# frontplatine_v0_2_140121.net
KiCad netlist of a schematic drawn in EAGLE
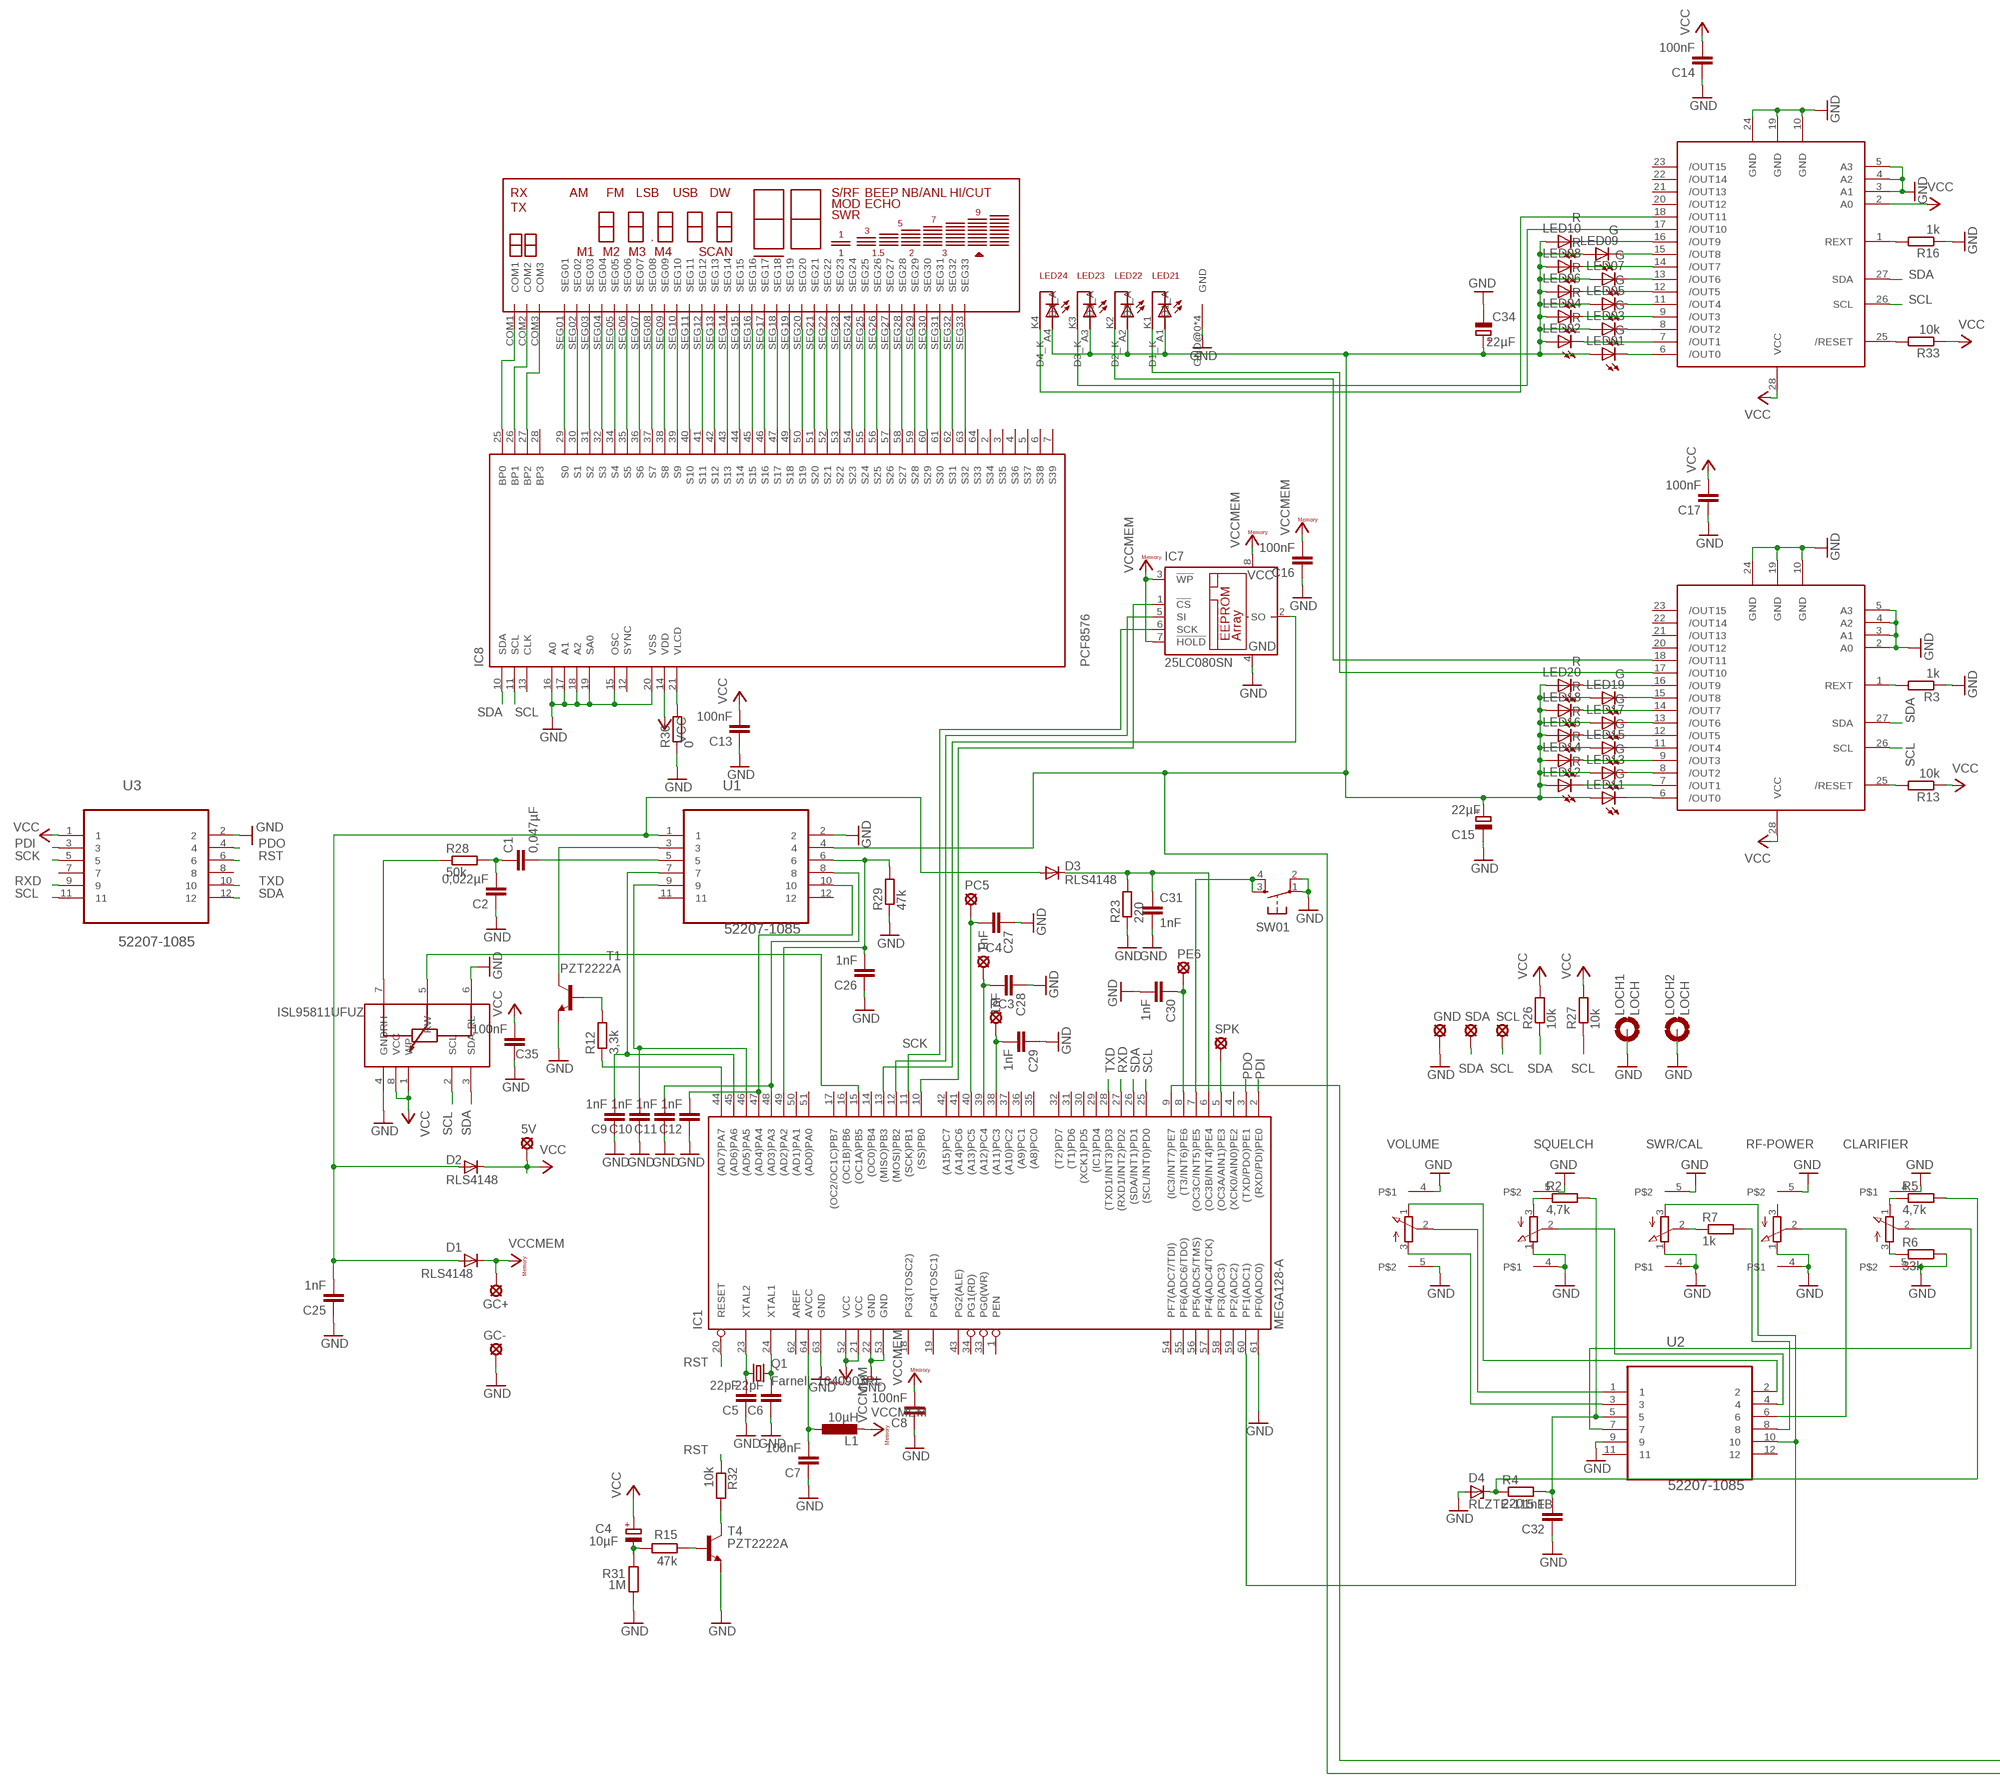
[diagram p0: schematic, sheet 1, part 1 of 2]
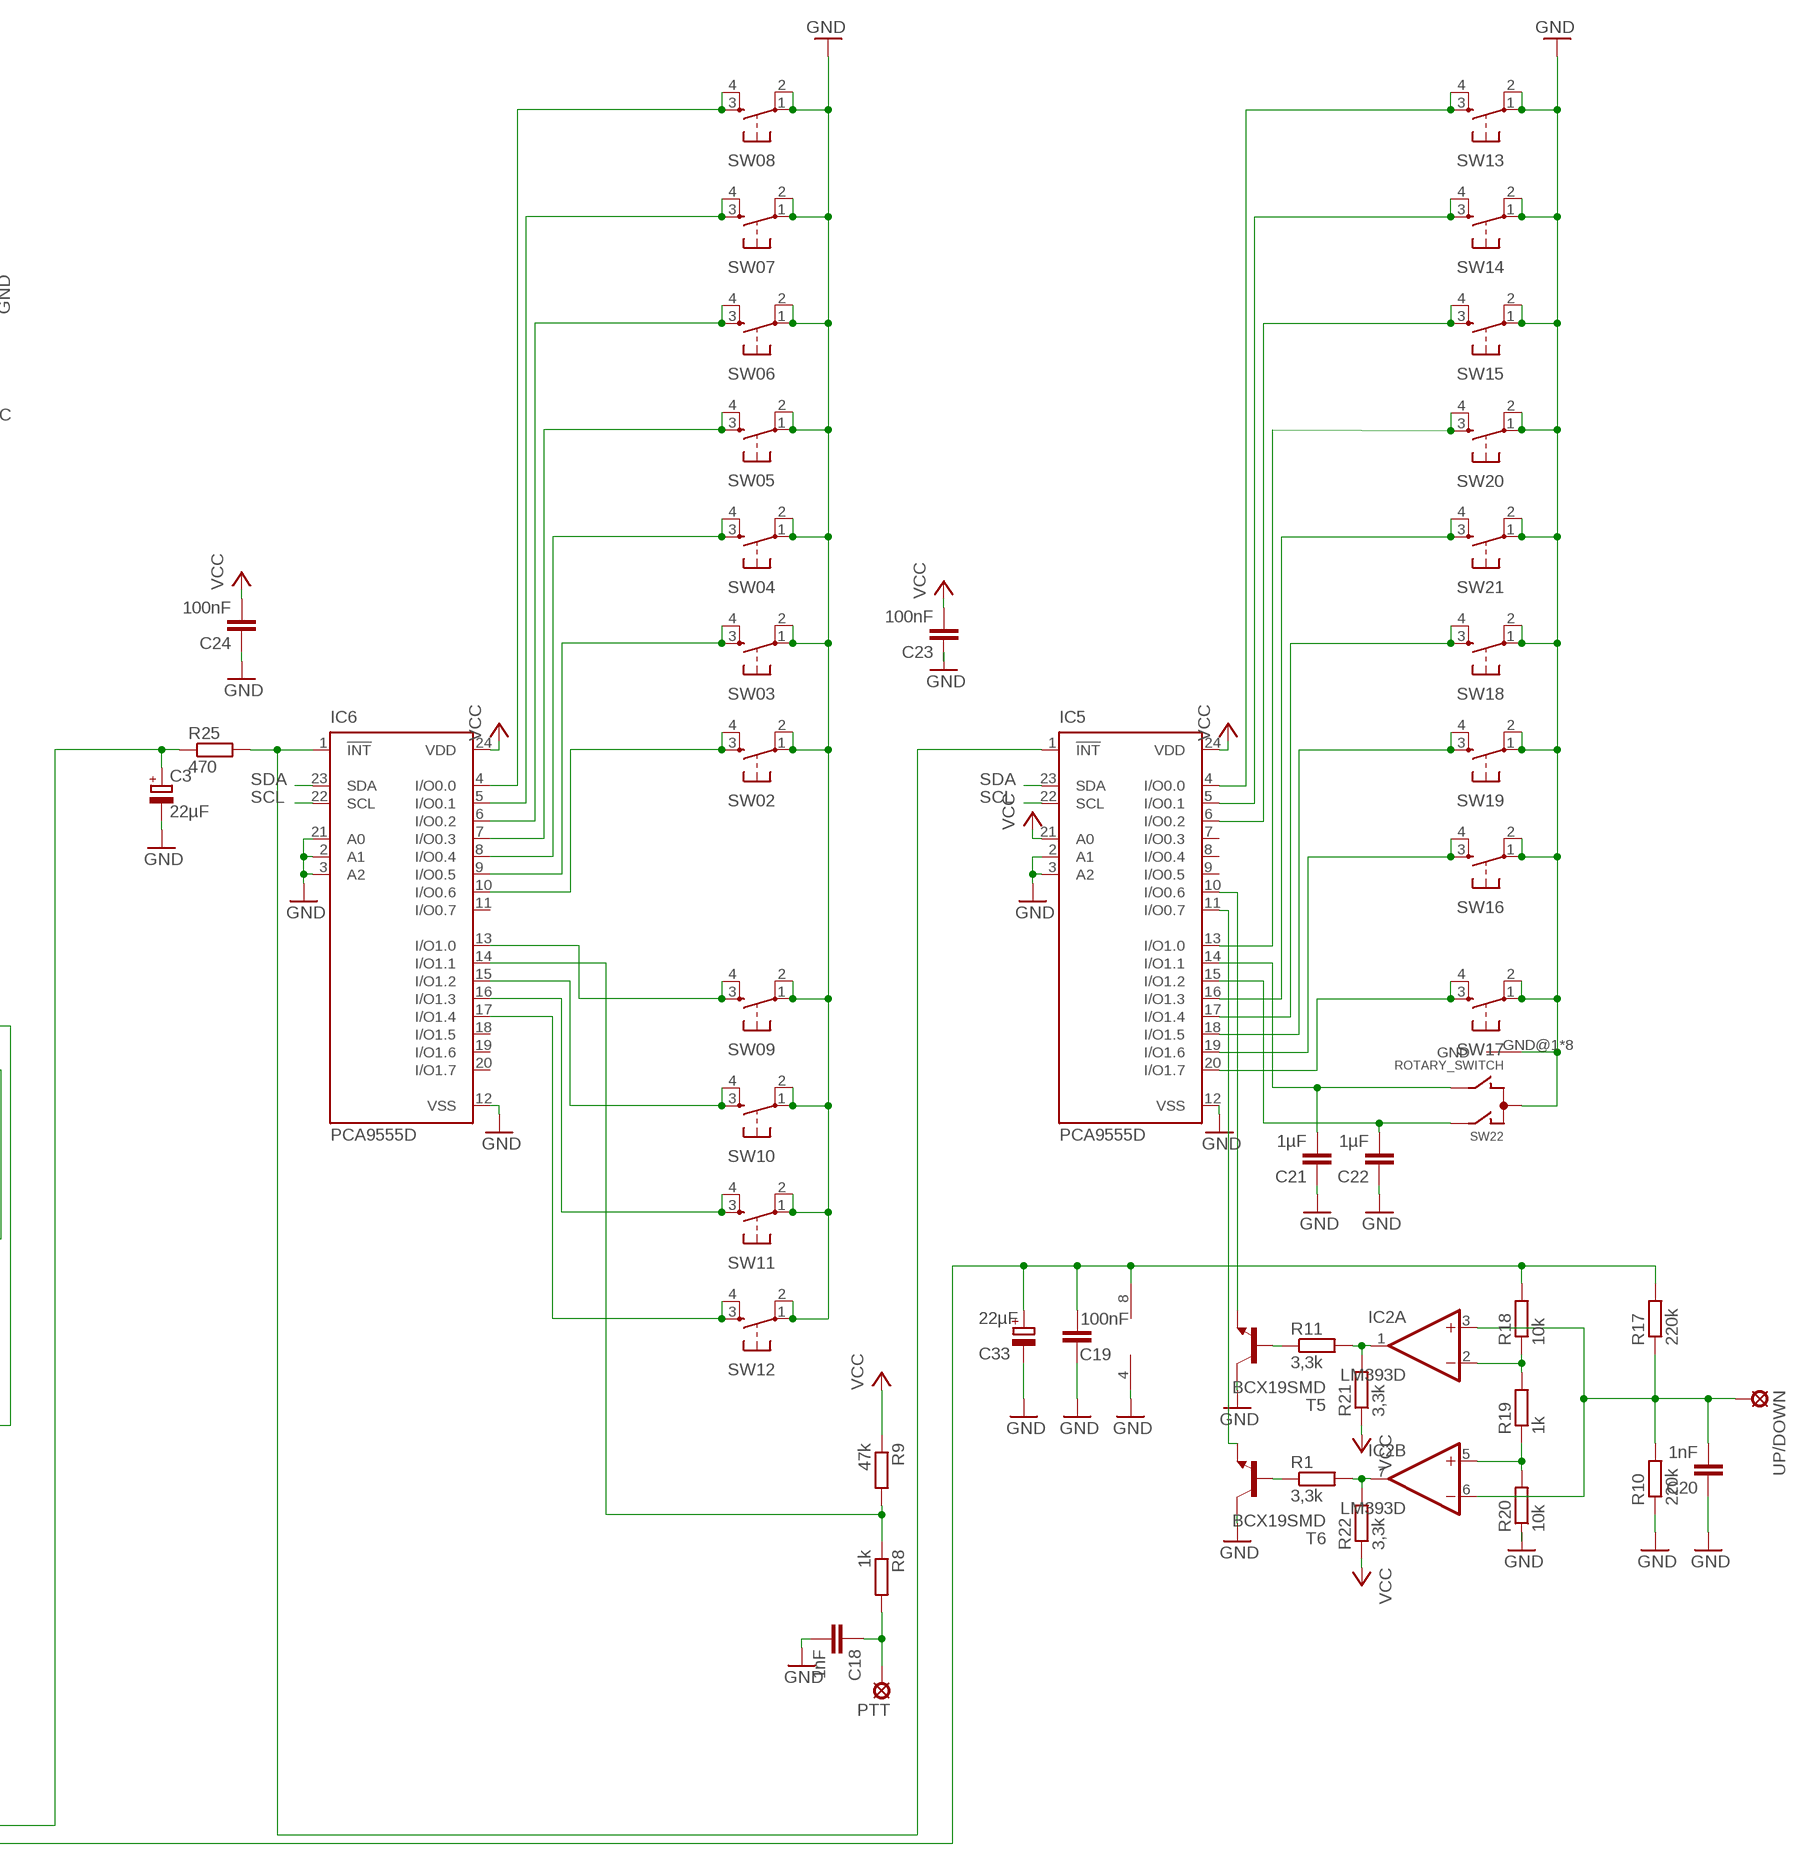
[diagram p1: schematic, sheet 1, part 2 of 2]

(export (version "E")
  (design (tool "Eeschema 10.0.6"))
  (components
    (comp (ref "5V")
      (value "SE11")
      (footprint "eagle-import:SE11")
      (libsource (lib "eagle-import") (part "SE11"))
    )
    (comp (ref "C1")
      (value "0,047µF")
      (footprint "eagle-import:C1206")
      (libsource (lib "eagle-import") (part "C-EUC1206"))
    )
    (comp (ref "C2")
      (value "0,022µF")
      (footprint "eagle-import:C1206")
      (libsource (lib "eagle-import") (part "resistor_C-EUC1206"))
    )
    (comp (ref "C3")
      (value "22µF")
      (footprint "eagle-import:CT3216")
      (libsource (lib "eagle-import") (part "CPOL-EUCT3216"))
    )
    (comp (ref "C4")
      (value "10µF")
      (footprint "eagle-import:CT3216")
      (libsource (lib "eagle-import") (part "CPOL-EUCT3216"))
    )
    (comp (ref "C5")
      (value "22pF")
      (footprint "eagle-import:C1206")
      (libsource (lib "eagle-import") (part "resistor_C-EUC1206"))
    )
    (comp (ref "C6")
      (value "22pF")
      (footprint "eagle-import:C1206")
      (libsource (lib "eagle-import") (part "resistor_C-EUC1206"))
    )
    (comp (ref "C7")
      (value "100nF")
      (footprint "eagle-import:C1206")
      (libsource (lib "eagle-import") (part "resistor_C-EUC1206"))
    )
    (comp (ref "C8")
      (value "100nF")
      (footprint "eagle-import:C1206")
      (libsource (lib "eagle-import") (part "resistor_C-EUC1206"))
    )
    (comp (ref "C9")
      (value "1nF")
      (footprint "eagle-import:C1206")
      (libsource (lib "eagle-import") (part "resistor_C-EUC1206"))
    )
    (comp (ref "C10")
      (value "1nF")
      (footprint "eagle-import:C1206")
      (libsource (lib "eagle-import") (part "resistor_C-EUC1206"))
    )
    (comp (ref "C11")
      (value "1nF")
      (footprint "eagle-import:C1206")
      (libsource (lib "eagle-import") (part "resistor_C-EUC1206"))
    )
    (comp (ref "C12")
      (value "1nF")
      (footprint "eagle-import:C1206")
      (libsource (lib "eagle-import") (part "resistor_C-EUC1206"))
    )
    (comp (ref "C13")
      (value "100nF")
      (footprint "eagle-import:C1206")
      (libsource (lib "eagle-import") (part "resistor_C-EUC1206"))
    )
    (comp (ref "C14")
      (value "100nF")
      (footprint "eagle-import:C1206")
      (libsource (lib "eagle-import") (part "resistor_C-EUC1206"))
    )
    (comp (ref "C15")
      (value "22µF")
      (footprint "eagle-import:CT3216")
      (libsource (lib "eagle-import") (part "CPOL-EUCT3216"))
    )
    (comp (ref "C16")
      (value "100nF")
      (footprint "eagle-import:C1206")
      (libsource (lib "eagle-import") (part "resistor_C-EUC1206"))
    )
    (comp (ref "C17")
      (value "100nF")
      (footprint "eagle-import:C1206")
      (libsource (lib "eagle-import") (part "resistor_C-EUC1206"))
    )
    (comp (ref "C18")
      (value "1nF")
      (footprint "eagle-import:C1206")
      (libsource (lib "eagle-import") (part "resistor_C-EUC1206"))
    )
    (comp (ref "C19")
      (value "100nF")
      (footprint "eagle-import:C1206")
      (libsource (lib "eagle-import") (part "resistor_C-EUC1206"))
    )
    (comp (ref "C20")
      (value "1nF")
      (footprint "eagle-import:C1206")
      (libsource (lib "eagle-import") (part "resistor_C-EUC1206"))
    )
    (comp (ref "C21")
      (value "1µF")
      (footprint "eagle-import:C1206")
      (libsource (lib "eagle-import") (part "resistor_C-EUC1206"))
    )
    (comp (ref "C22")
      (value "1µF")
      (footprint "eagle-import:C1206")
      (libsource (lib "eagle-import") (part "resistor_C-EUC1206"))
    )
    (comp (ref "C23")
      (value "100nF")
      (footprint "eagle-import:C1206")
      (libsource (lib "eagle-import") (part "resistor_C-EUC1206"))
    )
    (comp (ref "C24")
      (value "100nF")
      (footprint "eagle-import:C1206")
      (libsource (lib "eagle-import") (part "resistor_C-EUC1206"))
    )
    (comp (ref "C25")
      (value "1nF")
      (footprint "eagle-import:C1206")
      (libsource (lib "eagle-import") (part "resistor_C-EUC1206"))
    )
    (comp (ref "C26")
      (value "1nF")
      (footprint "eagle-import:C1206")
      (libsource (lib "eagle-import") (part "resistor_C-EUC1206"))
    )
    (comp (ref "C27")
      (value "1nF")
      (footprint "eagle-import:C1206")
      (libsource (lib "eagle-import") (part "resistor_C-EUC1206"))
    )
    (comp (ref "C28")
      (value "1nF")
      (footprint "eagle-import:C1206")
      (libsource (lib "eagle-import") (part "resistor_C-EUC1206"))
    )
    (comp (ref "C29")
      (value "1nF")
      (footprint "eagle-import:C1206")
      (libsource (lib "eagle-import") (part "resistor_C-EUC1206"))
    )
    (comp (ref "C30")
      (value "1nF")
      (footprint "eagle-import:C1206")
      (libsource (lib "eagle-import") (part "resistor_C-EUC1206"))
    )
    (comp (ref "C31")
      (value "1nF")
      (footprint "eagle-import:C1206")
      (libsource (lib "eagle-import") (part "resistor_C-EUC1206"))
    )
    (comp (ref "C32")
      (value "1nF")
      (footprint "eagle-import:C1206")
      (libsource (lib "eagle-import") (part "resistor_C-EUC1206"))
    )
    (comp (ref "C33")
      (value "22µF")
      (footprint "eagle-import:CT3216")
      (libsource (lib "eagle-import") (part "CPOL-EUCT3216"))
    )
    (comp (ref "C34")
      (value "22µF")
      (footprint "eagle-import:CT3216")
      (libsource (lib "eagle-import") (part "CPOL-EUCT3216"))
    )
    (comp (ref "C35")
      (value "100nF")
      (footprint "eagle-import:C1206")
      (libsource (lib "eagle-import") (part "resistor_C-EUC1206"))
    )
    (comp (ref "CLARIFIER")
      (value "POTI")
      (footprint "eagle-import:POTI")
      (libsource (lib "eagle-import") (part "POTI"))
    )
    (comp (ref "D1")
      (value "RLS4148")
      (footprint "eagle-import:SOD80C")
      (libsource (lib "eagle-import") (part "DIODE-SOD80C"))
    )
    (comp (ref "D2")
      (value "RLS4148")
      (footprint "eagle-import:SOD80C")
      (libsource (lib "eagle-import") (part "DIODE-SOD80C"))
    )
    (comp (ref "D3")
      (value "RLS4148")
      (footprint "eagle-import:SOD80C")
      (libsource (lib "eagle-import") (part "DIODE-SOD80C"))
    )
    (comp (ref "D4")
      (value "RLZTE-115.1B")
      (footprint "eagle-import:SOD80C")
      (libsource (lib "eagle-import") (part "ZENER-DIODESOD80C"))
    )
    (comp (ref "DISPLAY1")
      (value "DISPLAY")
      (footprint "eagle-import:DISPLAY")
      (libsource (lib "eagle-import") (part "DISPLAY"))
    )
    (comp (ref "GC+")
      (value "SE11")
      (footprint "eagle-import:SE11")
      (libsource (lib "eagle-import") (part "SE11"))
    )
    (comp (ref "GC-")
      (value "SE11")
      (footprint "eagle-import:SE11")
      (libsource (lib "eagle-import") (part "SE11"))
    )
    (comp (ref "GND")
      (value "SE11")
      (footprint "eagle-import:SE11")
      (libsource (lib "eagle-import") (part "SE11"))
    )
    (comp (ref "IC1")
      (value "MEGA128-A")
      (footprint "eagle-import:TQFP64")
      (fields (field (name "MPN") "ATMEGA128-16AU"))
      (libsource (lib "eagle-import") (part "MEGA128-A"))
    )
    (comp (ref "IC2")
      (value "LM393D")
      (footprint "eagle-import:SO08")
      (libsource (lib "eagle-import") (part "LM393D"))
    )
    (comp (ref "IC3")
      (value "TLC59116")
      (footprint "eagle-import:TSSOP28")
      (libsource (lib "eagle-import") (part "TLC59116"))
    )
    (comp (ref "IC4")
      (value "TLC59116")
      (footprint "eagle-import:TSSOP28")
      (libsource (lib "eagle-import") (part "TLC59116"))
    )
    (comp (ref "IC5")
      (value "PCA9555D")
      (footprint "eagle-import:SO24")
      (fields (field (name "MPN") "PCA9555DW"))
      (libsource (lib "eagle-import") (part "PCA9555D"))
    )
    (comp (ref "IC6")
      (value "PCA9555D")
      (footprint "eagle-import:SO24")
      (fields (field (name "MPN") "PCA9555DW"))
      (libsource (lib "eagle-import") (part "PCA9555D"))
    )
    (comp (ref "IC7")
      (value "25LC080SN")
      (footprint "eagle-import:SO-08")
      (fields
        (field (name "MF") "MICROCHIP")
        (field (name "MPN") "25LC080/SN")
        (field (name "MPN_1") "25LC080/SN")
        (field (name "OC_FARNELL") "1137302")
        (field (name "OC_NEWARK") "96K4092")
      )
      (libsource (lib "eagle-import") (part "25SNLC080"))
    )
    (comp (ref "IC8")
      (value "PCF8576")
      (footprint "eagle-import:LQFP-ST-64-2")
      (libsource (lib "eagle-import") (part "PCF8576"))
    )
    (comp (ref "L1")
      (value "10µH")
      (footprint "eagle-import:L1812")
      (libsource (lib "eagle-import") (part "L-EUL1812"))
    )
    (comp (ref "LED01")
      (value "G")
      (footprint "eagle-import:CHIPLED_1206")
      (libsource (lib "eagle-import") (part "LEDCHIPLED_1206"))
    )
    (comp (ref "LED02")
      (value "R")
      (footprint "eagle-import:CHIPLED_1206")
      (libsource (lib "eagle-import") (part "LEDCHIPLED_1206"))
    )
    (comp (ref "LED03")
      (value "G")
      (footprint "eagle-import:CHIPLED_1206")
      (libsource (lib "eagle-import") (part "LEDCHIPLED_1206"))
    )
    (comp (ref "LED04")
      (value "R")
      (footprint "eagle-import:CHIPLED_1206")
      (libsource (lib "eagle-import") (part "LEDCHIPLED_1206"))
    )
    (comp (ref "LED05")
      (value "G")
      (footprint "eagle-import:CHIPLED_1206")
      (libsource (lib "eagle-import") (part "LEDCHIPLED_1206"))
    )
    (comp (ref "LED06")
      (value "R")
      (footprint "eagle-import:CHIPLED_1206")
      (libsource (lib "eagle-import") (part "LEDCHIPLED_1206"))
    )
    (comp (ref "LED07")
      (value "G")
      (footprint "eagle-import:CHIPLED_1206")
      (libsource (lib "eagle-import") (part "LEDCHIPLED_1206"))
    )
    (comp (ref "LED08")
      (value "R")
      (footprint "eagle-import:CHIPLED_1206")
      (libsource (lib "eagle-import") (part "LEDCHIPLED_1206"))
    )
    (comp (ref "LED09")
      (value "G")
      (footprint "eagle-import:CHIPLED_1206")
      (libsource (lib "eagle-import") (part "LEDCHIPLED_1206"))
    )
    (comp (ref "LED10")
      (value "R")
      (footprint "eagle-import:CHIPLED_1206")
      (libsource (lib "eagle-import") (part "LEDCHIPLED_1206"))
    )
    (comp (ref "LED11")
      (value "G")
      (footprint "eagle-import:CHIPLED_1206")
      (libsource (lib "eagle-import") (part "LEDCHIPLED_1206"))
    )
    (comp (ref "LED12")
      (value "R")
      (footprint "eagle-import:CHIPLED_1206")
      (libsource (lib "eagle-import") (part "LEDCHIPLED_1206"))
    )
    (comp (ref "LED13")
      (value "G")
      (footprint "eagle-import:CHIPLED_1206")
      (libsource (lib "eagle-import") (part "LEDCHIPLED_1206"))
    )
    (comp (ref "LED14")
      (value "R")
      (footprint "eagle-import:CHIPLED_1206")
      (libsource (lib "eagle-import") (part "LEDCHIPLED_1206"))
    )
    (comp (ref "LED15")
      (value "G")
      (footprint "eagle-import:CHIPLED_1206")
      (libsource (lib "eagle-import") (part "LEDCHIPLED_1206"))
    )
    (comp (ref "LED16")
      (value "R")
      (footprint "eagle-import:CHIPLED_1206")
      (libsource (lib "eagle-import") (part "LEDCHIPLED_1206"))
    )
    (comp (ref "LED17")
      (value "G")
      (footprint "eagle-import:CHIPLED_1206")
      (libsource (lib "eagle-import") (part "LEDCHIPLED_1206"))
    )
    (comp (ref "LED18")
      (value "R")
      (footprint "eagle-import:CHIPLED_1206")
      (libsource (lib "eagle-import") (part "LEDCHIPLED_1206"))
    )
    (comp (ref "LED19")
      (value "G")
      (footprint "eagle-import:CHIPLED_1206")
      (libsource (lib "eagle-import") (part "LEDCHIPLED_1206"))
    )
    (comp (ref "LED20")
      (value "R")
      (footprint "eagle-import:CHIPLED_1206")
      (libsource (lib "eagle-import") (part "LEDCHIPLED_1206"))
    )
    (comp (ref "LOCH1")
      (value "LOCH")
      (footprint "eagle-import:LOCH")
      (libsource (lib "eagle-import") (part "LOCH"))
    )
    (comp (ref "LOCH2")
      (value "LOCH")
      (footprint "eagle-import:LOCH")
      (libsource (lib "eagle-import") (part "LOCH"))
    )
    (comp (ref "PC3")
      (value "SE11")
      (footprint "eagle-import:SE11")
      (libsource (lib "eagle-import") (part "SE11"))
    )
    (comp (ref "PC4")
      (value "SE11")
      (footprint "eagle-import:SE11")
      (libsource (lib "eagle-import") (part "SE11"))
    )
    (comp (ref "PC5")
      (value "SE11")
      (footprint "eagle-import:SE11")
      (libsource (lib "eagle-import") (part "SE11"))
    )
    (comp (ref "PE6")
      (value "SE11")
      (footprint "eagle-import:SE11")
      (libsource (lib "eagle-import") (part "SE11"))
    )
    (comp (ref "PTT")
      (value "SE11")
      (footprint "eagle-import:SE11")
      (libsource (lib "eagle-import") (part "SE11"))
    )
    (comp (ref "Q1")
      (value "Farnell: 1640903RL")
      (footprint "eagle-import:HC49UP")
      (libsource (lib "eagle-import") (part "CRYSTALHC49UP"))
    )
    (comp (ref "R1")
      (value "3,3k")
      (footprint "eagle-import:R1206")
      (libsource (lib "eagle-import") (part "resistor_R-EU_R1206"))
    )
    (comp (ref "R2")
      (value "4,7k")
      (footprint "eagle-import:R1206")
      (libsource (lib "eagle-import") (part "resistor_R-EU_R1206"))
    )
    (comp (ref "R3")
      (value "1k")
      (footprint "eagle-import:R1206")
      (libsource (lib "eagle-import") (part "R-EU_R1206"))
    )
    (comp (ref "R4")
      (value "220")
      (footprint "eagle-import:R1206")
      (libsource (lib "eagle-import") (part "resistor_R-EU_R1206"))
    )
    (comp (ref "R5")
      (value "4,7k")
      (footprint "eagle-import:R1206")
      (libsource (lib "eagle-import") (part "resistor_R-EU_R1206"))
    )
    (comp (ref "R6")
      (value "33k")
      (footprint "eagle-import:R1206")
      (libsource (lib "eagle-import") (part "resistor_R-EU_R1206"))
    )
    (comp (ref "R7")
      (value "1k")
      (footprint "eagle-import:R1206")
      (libsource (lib "eagle-import") (part "resistor_R-EU_R1206"))
    )
    (comp (ref "R8")
      (value "1k")
      (footprint "eagle-import:R1206")
      (libsource (lib "eagle-import") (part "resistor_R-EU_R1206"))
    )
    (comp (ref "R9")
      (value "47k")
      (footprint "eagle-import:R1206")
      (libsource (lib "eagle-import") (part "resistor_R-EU_R1206"))
    )
    (comp (ref "R10")
      (value "220k")
      (footprint "eagle-import:R1206")
      (libsource (lib "eagle-import") (part "resistor_R-EU_R1206"))
    )
    (comp (ref "R11")
      (value "3,3k")
      (footprint "eagle-import:R1206")
      (libsource (lib "eagle-import") (part "resistor_R-EU_R1206"))
    )
    (comp (ref "R12")
      (value "3,3k")
      (footprint "eagle-import:R1206")
      (libsource (lib "eagle-import") (part "resistor_R-EU_R1206"))
    )
    (comp (ref "R13")
      (value "10k")
      (footprint "eagle-import:R1206")
      (libsource (lib "eagle-import") (part "resistor_R-EU_R1206"))
    )
    (comp (ref "R15")
      (value "47k")
      (footprint "eagle-import:R1206")
      (libsource (lib "eagle-import") (part "resistor_R-EU_R1206"))
    )
    (comp (ref "R16")
      (value "1k")
      (footprint "eagle-import:R1206")
      (libsource (lib "eagle-import") (part "R-EU_R1206"))
    )
    (comp (ref "R17")
      (value "220k")
      (footprint "eagle-import:R1206")
      (libsource (lib "eagle-import") (part "resistor_R-EU_R1206"))
    )
    (comp (ref "R18")
      (value "10k")
      (footprint "eagle-import:R1206")
      (libsource (lib "eagle-import") (part "resistor_R-EU_R1206"))
    )
    (comp (ref "R19")
      (value "1k")
      (footprint "eagle-import:R1206")
      (libsource (lib "eagle-import") (part "resistor_R-EU_R1206"))
    )
    (comp (ref "R20")
      (value "10k")
      (footprint "eagle-import:R1206")
      (libsource (lib "eagle-import") (part "resistor_R-EU_R1206"))
    )
    (comp (ref "R21")
      (value "3,3k")
      (footprint "eagle-import:R1206")
      (libsource (lib "eagle-import") (part "resistor_R-EU_R1206"))
    )
    (comp (ref "R22")
      (value "3,3k")
      (footprint "eagle-import:R1206")
      (libsource (lib "eagle-import") (part "resistor_R-EU_R1206"))
    )
    (comp (ref "R23")
      (value "220")
      (footprint "eagle-import:R1206")
      (libsource (lib "eagle-import") (part "resistor_R-EU_R1206"))
    )
    (comp (ref "R25")
      (value "470")
      (footprint "eagle-import:R1206")
      (libsource (lib "eagle-import") (part "resistor_R-EU_R1206"))
    )
    (comp (ref "R26")
      (value "10k")
      (footprint "eagle-import:R1206")
      (libsource (lib "eagle-import") (part "resistor_R-EU_R1206"))
    )
    (comp (ref "R27")
      (value "10k")
      (footprint "eagle-import:R1206")
      (libsource (lib "eagle-import") (part "resistor_R-EU_R1206"))
    )
    (comp (ref "R28")
      (value "50k")
      (footprint "eagle-import:R1206")
      (libsource (lib "eagle-import") (part "resistor_R-EU_R1206"))
    )
    (comp (ref "R29")
      (value "47k")
      (footprint "eagle-import:R1206")
      (libsource (lib "eagle-import") (part "resistor_R-EU_R1206"))
    )
    (comp (ref "R30")
      (value "0")
      (footprint "eagle-import:R1206")
      (libsource (lib "eagle-import") (part "resistor_R-EU_R1206"))
    )
    (comp (ref "R31")
      (value "1M")
      (footprint "eagle-import:R1206")
      (libsource (lib "eagle-import") (part "resistor_R-EU_R1206"))
    )
    (comp (ref "R32")
      (value "10k")
      (footprint "eagle-import:R1206")
      (libsource (lib "eagle-import") (part "resistor_R-EU_R1206"))
    )
    (comp (ref "R33")
      (value "10k")
      (footprint "eagle-import:R1206")
      (libsource (lib "eagle-import") (part "resistor_R-EU_R1206"))
    )
    (comp (ref "RF-POWER")
      (value "POTI")
      (footprint "eagle-import:POTI")
      (libsource (lib "eagle-import") (part "POTI"))
    )
    (comp (ref "SCL")
      (value "SE11")
      (footprint "eagle-import:SE11")
      (libsource (lib "eagle-import") (part "SE11"))
    )
    (comp (ref "SDA")
      (value "SE11")
      (footprint "eagle-import:SE11")
      (libsource (lib "eagle-import") (part "SE11"))
    )
    (comp (ref "SPK")
      (value "SE11")
      (footprint "eagle-import:SE11")
      (libsource (lib "eagle-import") (part "SE11"))
    )
    (comp (ref "SQUELCH")
      (value "POTI")
      (footprint "eagle-import:POTI")
      (libsource (lib "eagle-import") (part "POTI"))
    )
    (comp (ref "SW01")
      (value "TASTER")
      (footprint "eagle-import:TASTER")
      (libsource (lib "eagle-import") (part "TASTER"))
    )
    (comp (ref "SW02")
      (value "TASTER")
      (footprint "eagle-import:TASTER")
      (libsource (lib "eagle-import") (part "TASTER"))
    )
    (comp (ref "SW03")
      (value "TASTER")
      (footprint "eagle-import:TASTER")
      (libsource (lib "eagle-import") (part "TASTER"))
    )
    (comp (ref "SW04")
      (value "TASTER")
      (footprint "eagle-import:TASTER")
      (libsource (lib "eagle-import") (part "TASTER"))
    )
    (comp (ref "SW05")
      (value "TASTER")
      (footprint "eagle-import:TASTER")
      (libsource (lib "eagle-import") (part "TASTER"))
    )
    (comp (ref "SW06")
      (value "TASTER")
      (footprint "eagle-import:TASTER")
      (libsource (lib "eagle-import") (part "TASTER"))
    )
    (comp (ref "SW07")
      (value "TASTER")
      (footprint "eagle-import:TASTER")
      (libsource (lib "eagle-import") (part "TASTER"))
    )
    (comp (ref "SW08")
      (value "TASTER")
      (footprint "eagle-import:TASTER")
      (libsource (lib "eagle-import") (part "TASTER"))
    )
    (comp (ref "SW09")
      (value "TASTER")
      (footprint "eagle-import:TASTER")
      (libsource (lib "eagle-import") (part "TASTER"))
    )
    (comp (ref "SW10")
      (value "TASTER")
      (footprint "eagle-import:TASTER")
      (libsource (lib "eagle-import") (part "TASTER"))
    )
    (comp (ref "SW11")
      (value "TASTER")
      (footprint "eagle-import:TASTER")
      (libsource (lib "eagle-import") (part "TASTER"))
    )
    (comp (ref "SW12")
      (value "TASTER")
      (footprint "eagle-import:TASTER")
      (libsource (lib "eagle-import") (part "TASTER"))
    )
    (comp (ref "SW13")
      (value "TASTER")
      (footprint "eagle-import:TASTER")
      (libsource (lib "eagle-import") (part "TASTER"))
    )
    (comp (ref "SW14")
      (value "TASTER")
      (footprint "eagle-import:TASTER")
      (libsource (lib "eagle-import") (part "TASTER"))
    )
    (comp (ref "SW15")
      (value "TASTER")
      (footprint "eagle-import:TASTER")
      (libsource (lib "eagle-import") (part "TASTER"))
    )
    (comp (ref "SW16")
      (value "TASTER")
      (footprint "eagle-import:TASTER")
      (libsource (lib "eagle-import") (part "TASTER"))
    )
    (comp (ref "SW17")
      (value "TASTER")
      (footprint "eagle-import:TASTER")
      (libsource (lib "eagle-import") (part "TASTER"))
    )
    (comp (ref "SW18")
      (value "TASTER")
      (footprint "eagle-import:TASTER")
      (libsource (lib "eagle-import") (part "TASTER"))
    )
    (comp (ref "SW19")
      (value "TASTER")
      (footprint "eagle-import:TASTER")
      (libsource (lib "eagle-import") (part "TASTER"))
    )
    (comp (ref "SW20")
      (value "TASTER")
      (footprint "eagle-import:TASTER")
      (libsource (lib "eagle-import") (part "TASTER"))
    )
    (comp (ref "SW21")
      (value "TASTER")
      (footprint "eagle-import:TASTER")
      (libsource (lib "eagle-import") (part "TASTER"))
    )
    (comp (ref "SW22")
      (value "ROTARY_SWITCH")
      (footprint "eagle-import:ROTARY_SWITCH")
      (libsource (lib "eagle-import") (part "ROTARY_SWITCH"))
    )
    (comp (ref "SWR/CAL")
      (value "POTI")
      (footprint "eagle-import:POTI")
      (libsource (lib "eagle-import") (part "POTI"))
    )
    (comp (ref "T1")
      (value "PZT2222A")
      (footprint "eagle-import:SOT223")
      (libsource (lib "eagle-import") (part "-NPN-SOT223PZT2222A"))
    )
    (comp (ref "T4")
      (value "PZT2222A")
      (footprint "eagle-import:SOT223")
      (libsource (lib "eagle-import") (part "-NPN-SOT223PZT2222A"))
    )
    (comp (ref "T5")
      (value "BCX19SMD")
      (footprint "eagle-import:SOT23-BEC")
      (libsource (lib "eagle-import") (part "BCX19SMD"))
    )
    (comp (ref "T6")
      (value "BCX19SMD")
      (footprint "eagle-import:SOT23-BEC")
      (libsource (lib "eagle-import") (part "BCX19SMD"))
    )
    (comp (ref "U$1")
      (value "ISL95811UFUZ")
      (footprint "eagle-import:MSOP8")
      (libsource (lib "eagle-import") (part "ISL95811UFUZ"))
    )
    (comp (ref "U1")
      (value "52207-1085")
      (footprint "eagle-import:MOLEX_52207-1085")
      (fields
        (field (name "MPN") "52207-1085")
        (field (name "OC_FARNELL") "1079938")
        (field (name "OC_NEWARK") "58J9503")
        (field (name "PACKAGE") "SOCKET FPC, SMT, 1MM, 10 WAY")
      )
      (libsource (lib "eagle-import") (part "52207-1085"))
    )
    (comp (ref "U2")
      (value "52207-1085")
      (footprint "eagle-import:MOLEX_52207-1085")
      (fields
        (field (name "MPN") "52207-1085")
        (field (name "OC_FARNELL") "1079938")
        (field (name "OC_NEWARK") "58J9503")
        (field (name "PACKAGE") "SOCKET FPC, SMT, 1MM, 10 WAY")
      )
      (libsource (lib "eagle-import") (part "52207-1085"))
    )
    (comp (ref "U3")
      (value "52207-1085")
      (footprint "eagle-import:MOLEX_52207-1085")
      (libsource (lib "eagle-import") (part "52207-1085"))
    )
    (comp (ref "UP/DOWN")
      (value "SE11")
      (footprint "eagle-import:SE11")
      (libsource (lib "eagle-import") (part "SE11"))
    )
    (comp (ref "VOLUME")
      (value "POTI")
      (footprint "eagle-import:POTI")
      (libsource (lib "eagle-import") (part "POTI"))
    )
  )
  (nets
    (net (code "1") (name "/PDI") (class "Default")
      (node (ref "IC1") (pin "2") (pinfunction "(RXD/PDI)PE0_2") (pintype "bidirectional"))
      (node (ref "U3") (pin "3") (pinfunction "3_3") (pintype "passive"))
    )
    (net (code "2") (name "/PDO") (class "Default")
      (node (ref "IC1") (pin "3") (pinfunction "(TXD/PDO)PE1_3") (pintype "bidirectional"))
      (node (ref "U3") (pin "4") (pinfunction "4_4") (pintype "passive"))
    )
    (net (code "3") (name "/RST") (class "Default")
      (node (ref "IC1") (pin "20") (pinfunction "RESET_20") (pintype "input"))
      (node (ref "R32") (pin "1") (pinfunction "1_1") (pintype "passive"))
      (node (ref "U3") (pin "6") (pinfunction "6_6") (pintype "passive"))
    )
    (net (code "4") (name "/RXD") (class "Default")
      (node (ref "IC1") (pin "27") (pinfunction "(RXD1/INT2)PD2_27") (pintype "bidirectional"))
      (node (ref "U3") (pin "9") (pinfunction "9_9") (pintype "passive"))
    )
    (net (code "5") (name "/SCK") (class "Default")
      (node (ref "IC1") (pin "11") (pinfunction "(SCK)PB1_11") (pintype "bidirectional"))
      (node (ref "IC7") (pin "6") (pinfunction "SCK_6") (pintype "input"))
      (node (ref "U3") (pin "5") (pinfunction "5_5") (pintype "passive"))
    )
    (net (code "6") (name "/SCL") (class "Default")
      (node (ref "IC1") (pin "25") (pinfunction "(SCL/INT0)PD0_25") (pintype "bidirectional"))
      (node (ref "IC3") (pin "26") (pinfunction "SCL_26") (pintype "bidirectional"))
      (node (ref "IC4") (pin "26") (pinfunction "SCL_26") (pintype "bidirectional"))
      (node (ref "IC5") (pin "22") (pinfunction "SCL_22") (pintype "input"))
      (node (ref "IC6") (pin "22") (pinfunction "SCL_22") (pintype "input"))
      (node (ref "IC8") (pin "11") (pinfunction "SCL_11") (pintype "input"))
      (node (ref "R27") (pin "1") (pinfunction "1_1") (pintype "passive"))
      (node (ref "SCL") (pin "MP") (pinfunction "MP_MP") (pintype "passive"))
      (node (ref "U$1") (pin "2") (pinfunction "SCL_2") (pintype "bidirectional"))
      (node (ref "U3") (pin "11") (pinfunction "11_11") (pintype "passive"))
    )
    (net (code "7") (name "/SDA") (class "Default")
      (node (ref "IC1") (pin "26") (pinfunction "(SDA/INT1)PD1_26") (pintype "bidirectional"))
      (node (ref "IC3") (pin "27") (pinfunction "SDA_27") (pintype "bidirectional"))
      (node (ref "IC4") (pin "27") (pinfunction "SDA_27") (pintype "bidirectional"))
      (node (ref "IC5") (pin "23") (pinfunction "SDA_23") (pintype "bidirectional"))
      (node (ref "IC6") (pin "23") (pinfunction "SDA_23") (pintype "bidirectional"))
      (node (ref "IC8") (pin "10") (pinfunction "SDA_10") (pintype "bidirectional"))
      (node (ref "R26") (pin "1") (pinfunction "1_1") (pintype "passive"))
      (node (ref "SDA") (pin "MP") (pinfunction "MP_MP") (pintype "passive"))
      (node (ref "U$1") (pin "3") (pinfunction "SDA_3") (pintype "input"))
      (node (ref "U3") (pin "12") (pinfunction "12_12") (pintype "passive"))
    )
    (net (code "8") (name "/TXD") (class "Default")
      (node (ref "IC1") (pin "28") (pinfunction "(TXD1/INT3)PD3_28") (pintype "bidirectional"))
      (node (ref "U3") (pin "10") (pinfunction "10_10") (pintype "passive"))
    )
    (net (code "9") (name "GND") (class "Default")
      (node (ref "C10") (pin "1") (pinfunction "1_1") (pintype "passive"))
      (node (ref "C11") (pin "1") (pinfunction "1_1") (pintype "passive"))
      (node (ref "C12") (pin "1") (pinfunction "1_1") (pintype "passive"))
      (node (ref "C13") (pin "1") (pinfunction "1_1") (pintype "passive"))
      (node (ref "C14") (pin "1") (pinfunction "1_1") (pintype "passive"))
      (node (ref "C15") (pin "-") (pinfunction "-_-") (pintype "passive"))
      (node (ref "C16") (pin "1") (pinfunction "1_1") (pintype "passive"))
      (node (ref "C17") (pin "1") (pinfunction "1_1") (pintype "passive"))
      (node (ref "C18") (pin "2") (pinfunction "2_2") (pintype "passive"))
      (node (ref "C19") (pin "1") (pinfunction "1_1") (pintype "passive"))
      (node (ref "C2") (pin "1") (pinfunction "1_1") (pintype "passive"))
      (node (ref "C20") (pin "1") (pinfunction "1_1") (pintype "passive"))
      (node (ref "C21") (pin "1") (pinfunction "1_1") (pintype "passive"))
      (node (ref "C22") (pin "1") (pinfunction "1_1") (pintype "passive"))
      (node (ref "C23") (pin "1") (pinfunction "1_1") (pintype "passive"))
      (node (ref "C24") (pin "1") (pinfunction "1_1") (pintype "passive"))
      (node (ref "C25") (pin "1") (pinfunction "1_1") (pintype "passive"))
      (node (ref "C26") (pin "1") (pinfunction "1_1") (pintype "passive"))
      (node (ref "C27") (pin "1") (pinfunction "1_1") (pintype "passive"))
      (node (ref "C28") (pin "1") (pinfunction "1_1") (pintype "passive"))
      (node (ref "C29") (pin "1") (pinfunction "1_1") (pintype "passive"))
      (node (ref "C3") (pin "-") (pinfunction "-_-") (pintype "passive"))
      (node (ref "C30") (pin "2") (pinfunction "2_2") (pintype "passive"))
      (node (ref "C31") (pin "2") (pinfunction "2_2") (pintype "passive"))
      (node (ref "C32") (pin "1") (pinfunction "1_1") (pintype "passive"))
      (node (ref "C33") (pin "-") (pinfunction "-_-") (pintype "passive"))
      (node (ref "C34") (pin "-") (pinfunction "-_-") (pintype "passive"))
      (node (ref "C35") (pin "1") (pinfunction "1_1") (pintype "passive"))
      (node (ref "C5") (pin "1") (pinfunction "1_1") (pintype "passive"))
      (node (ref "C6") (pin "1") (pinfunction "1_1") (pintype "passive"))
      (node (ref "C7") (pin "1") (pinfunction "1_1") (pintype "passive"))
      (node (ref "C8") (pin "1") (pinfunction "1_1") (pintype "passive"))
      (node (ref "C9") (pin "1") (pinfunction "1_1") (pintype "passive"))
      (node (ref "CLARIFIER") (pin "4") (pinfunction "P$1_4") (pintype "power_in"))
      (node (ref "CLARIFIER") (pin "5") (pinfunction "P$2_5") (pintype "power_in"))
      (node (ref "D4") (pin "A") (pinfunction "A_A") (pintype "passive"))
      (node (ref "DISPLAY1") (pin "GND@0") (pinfunction "GND_GND@0") (pintype "power_in"))
      (node (ref "DISPLAY1") (pin "GND@3") (pinfunction "GND_GND@3") (pintype "power_in"))
      (node (ref "DISPLAY1") (pin "GND@6") (pinfunction "GND_GND@6") (pintype "power_in"))
      (node (ref "DISPLAY1") (pin "GND@7") (pinfunction "GND_GND@7") (pintype "power_in"))
      (node (ref "GC-") (pin "MP") (pinfunction "MP_MP") (pintype "passive"))
      (node (ref "GND") (pin "MP") (pinfunction "MP_MP") (pintype "passive"))
      (node (ref "IC1") (pin "22") (pinfunction "GND_22") (pintype "power_in"))
      (node (ref "IC1") (pin "53") (pinfunction "GND_53") (pintype "power_in"))
      (node (ref "IC1") (pin "61") (pinfunction "PF0(ADC0)_61") (pintype "input"))
      (node (ref "IC1") (pin "63") (pinfunction "GND_63") (pintype "power_in"))
      (node (ref "IC2") (pin "4") (pinfunction "V-_4") (pintype "power_in"))
      (node (ref "IC3") (pin "10") (pinfunction "GND_10") (pintype "bidirectional"))
      (node (ref "IC3") (pin "19") (pinfunction "GND_19") (pintype "bidirectional"))
      (node (ref "IC3") (pin "2") (pinfunction "A0_2") (pintype "bidirectional"))
      (node (ref "IC3") (pin "24") (pinfunction "GND_24") (pintype "bidirectional"))
      (node (ref "IC3") (pin "3") (pinfunction "A1_3") (pintype "bidirectional"))
      (node (ref "IC3") (pin "4") (pinfunction "A2_4") (pintype "bidirectional"))
      (node (ref "IC3") (pin "5") (pinfunction "A3_5") (pintype "bidirectional"))
      (node (ref "IC4") (pin "10") (pinfunction "GND_10") (pintype "bidirectional"))
      (node (ref "IC4") (pin "19") (pinfunction "GND_19") (pintype "bidirectional"))
      (node (ref "IC4") (pin "24") (pinfunction "GND_24") (pintype "bidirectional"))
      (node (ref "IC4") (pin "3") (pinfunction "A1_3") (pintype "bidirectional"))
      (node (ref "IC4") (pin "4") (pinfunction "A2_4") (pintype "bidirectional"))
      (node (ref "IC4") (pin "5") (pinfunction "A3_5") (pintype "bidirectional"))
      (node (ref "IC5") (pin "12") (pinfunction "VSS_12") (pintype "power_in"))
      (node (ref "IC5") (pin "2") (pinfunction "A1_2") (pintype "input"))
      (node (ref "IC5") (pin "3") (pinfunction "A2_3") (pintype "input"))
      (node (ref "IC6") (pin "12") (pinfunction "VSS_12") (pintype "power_in"))
      (node (ref "IC6") (pin "2") (pinfunction "A1_2") (pintype "input"))
      (node (ref "IC6") (pin "21") (pinfunction "A0_21") (pintype "input"))
      (node (ref "IC6") (pin "3") (pinfunction "A2_3") (pintype "input"))
      (node (ref "IC7") (pin "4") (pinfunction "GND_4") (pintype "power_in"))
      (node (ref "IC8") (pin "15") (pinfunction "OSC_15") (pintype "input"))
      (node (ref "IC8") (pin "16") (pinfunction "A0_16") (pintype "input"))
      (node (ref "IC8") (pin "17") (pinfunction "A1_17") (pintype "input"))
      (node (ref "IC8") (pin "18") (pinfunction "A2_18") (pintype "input"))
      (node (ref "IC8") (pin "19") (pinfunction "SA0_19") (pintype "input"))
      (node (ref "IC8") (pin "20") (pinfunction "VSS_20") (pintype "power_in"))
      (node (ref "LOCH1") (pin "B3,0") (pinfunction "MOUNT_B3,0") (pintype "passive"))
      (node (ref "LOCH2") (pin "B3,0") (pinfunction "MOUNT_B3,0") (pintype "passive"))
      (node (ref "R10") (pin "1") (pinfunction "1_1") (pintype "passive"))
      (node (ref "R16") (pin "1") (pinfunction "1_1") (pintype "passive"))
      (node (ref "R20") (pin "1") (pinfunction "1_1") (pintype "passive"))
      (node (ref "R23") (pin "1") (pinfunction "1_1") (pintype "passive"))
      (node (ref "R29") (pin "1") (pinfunction "1_1") (pintype "passive"))
      (node (ref "R3") (pin "1") (pinfunction "1_1") (pintype "passive"))
      (node (ref "R30") (pin "1") (pinfunction "1_1") (pintype "passive"))
      (node (ref "R31") (pin "2") (pinfunction "2_2") (pintype "passive"))
      (node (ref "R6") (pin "2") (pinfunction "2_2") (pintype "passive"))
      (node (ref "RF-POWER") (pin "1") (pinfunction "E_1") (pintype "passive"))
      (node (ref "RF-POWER") (pin "4") (pinfunction "P$1_4") (pintype "power_in"))
      (node (ref "RF-POWER") (pin "5") (pinfunction "P$2_5") (pintype "power_in"))
      (node (ref "SQUELCH") (pin "1") (pinfunction "E_1") (pintype "passive"))
      (node (ref "SQUELCH") (pin "4") (pinfunction "P$1_4") (pintype "power_in"))
      (node (ref "SQUELCH") (pin "5") (pinfunction "P$2_5") (pintype "power_in"))
      (node (ref "SW01") (pin "1") (pinfunction "1_1") (pintype "passive"))
      (node (ref "SW01") (pin "2") (pinfunction "2_2") (pintype "passive"))
      (node (ref "SW02") (pin "1") (pinfunction "1_1") (pintype "passive"))
      (node (ref "SW02") (pin "2") (pinfunction "2_2") (pintype "passive"))
      (node (ref "SW03") (pin "1") (pinfunction "1_1") (pintype "passive"))
      (node (ref "SW03") (pin "2") (pinfunction "2_2") (pintype "passive"))
      (node (ref "SW04") (pin "1") (pinfunction "1_1") (pintype "passive"))
      (node (ref "SW04") (pin "2") (pinfunction "2_2") (pintype "passive"))
      (node (ref "SW05") (pin "1") (pinfunction "1_1") (pintype "passive"))
      (node (ref "SW05") (pin "2") (pinfunction "2_2") (pintype "passive"))
      (node (ref "SW06") (pin "1") (pinfunction "1_1") (pintype "passive"))
      (node (ref "SW06") (pin "2") (pinfunction "2_2") (pintype "passive"))
      (node (ref "SW07") (pin "1") (pinfunction "1_1") (pintype "passive"))
      (node (ref "SW07") (pin "2") (pinfunction "2_2") (pintype "passive"))
      (node (ref "SW08") (pin "1") (pinfunction "1_1") (pintype "passive"))
      (node (ref "SW08") (pin "2") (pinfunction "2_2") (pintype "passive"))
      (node (ref "SW09") (pin "1") (pinfunction "1_1") (pintype "passive"))
      (node (ref "SW09") (pin "2") (pinfunction "2_2") (pintype "passive"))
      (node (ref "SW10") (pin "1") (pinfunction "1_1") (pintype "passive"))
      (node (ref "SW10") (pin "2") (pinfunction "2_2") (pintype "passive"))
      (node (ref "SW11") (pin "1") (pinfunction "1_1") (pintype "passive"))
      (node (ref "SW11") (pin "2") (pinfunction "2_2") (pintype "passive"))
      (node (ref "SW12") (pin "1") (pinfunction "1_1") (pintype "passive"))
      (node (ref "SW12") (pin "2") (pinfunction "2_2") (pintype "passive"))
      (node (ref "SW13") (pin "1") (pinfunction "1_1") (pintype "passive"))
      (node (ref "SW13") (pin "2") (pinfunction "2_2") (pintype "passive"))
      (node (ref "SW14") (pin "1") (pinfunction "1_1") (pintype "passive"))
      (node (ref "SW14") (pin "2") (pinfunction "2_2") (pintype "passive"))
      (node (ref "SW15") (pin "1") (pinfunction "1_1") (pintype "passive"))
      (node (ref "SW15") (pin "2") (pinfunction "2_2") (pintype "passive"))
      (node (ref "SW16") (pin "1") (pinfunction "1_1") (pintype "passive"))
      (node (ref "SW16") (pin "2") (pinfunction "2_2") (pintype "passive"))
      (node (ref "SW17") (pin "1") (pinfunction "1_1") (pintype "passive"))
      (node (ref "SW17") (pin "2") (pinfunction "2_2") (pintype "passive"))
      (node (ref "SW18") (pin "1") (pinfunction "1_1") (pintype "passive"))
      (node (ref "SW18") (pin "2") (pinfunction "2_2") (pintype "passive"))
      (node (ref "SW19") (pin "1") (pinfunction "1_1") (pintype "passive"))
      (node (ref "SW19") (pin "2") (pinfunction "2_2") (pintype "passive"))
      (node (ref "SW20") (pin "1") (pinfunction "1_1") (pintype "passive"))
      (node (ref "SW20") (pin "2") (pinfunction "2_2") (pintype "passive"))
      (node (ref "SW21") (pin "1") (pinfunction "1_1") (pintype "passive"))
      (node (ref "SW21") (pin "2") (pinfunction "2_2") (pintype "passive"))
      (node (ref "SW22") (pin "C") (pinfunction "C_C") (pintype "passive"))
      (node (ref "SW22") (pin "GND@1") (pinfunction "GND_GND@1") (pintype "power_in"))
      (node (ref "SW22") (pin "GND@2") (pinfunction "GND_GND@2") (pintype "power_in"))
      (node (ref "SW22") (pin "GND@3") (pinfunction "GND_GND@3") (pintype "power_in"))
      (node (ref "SW22") (pin "GND@4") (pinfunction "GND_GND@4") (pintype "power_in"))
      (node (ref "SW22") (pin "GND@5") (pinfunction "GND_GND@5") (pintype "power_in"))
      (node (ref "SW22") (pin "GND@6") (pinfunction "GND_GND@6") (pintype "power_in"))
      (node (ref "SW22") (pin "GND@7") (pinfunction "GND_GND@7") (pintype "power_in"))
      (node (ref "SW22") (pin "GND@8") (pinfunction "GND_GND@8") (pintype "power_in"))
      (node (ref "SWR/CAL") (pin "1") (pinfunction "E_1") (pintype "passive"))
      (node (ref "SWR/CAL") (pin "4") (pinfunction "P$1_4") (pintype "power_in"))
      (node (ref "SWR/CAL") (pin "5") (pinfunction "P$2_5") (pintype "power_in"))
      (node (ref "T1") (pin "3") (pinfunction "E_3") (pintype "passive"))
      (node (ref "T4") (pin "3") (pinfunction "E_3") (pintype "passive"))
      (node (ref "T5") (pin "C") (pinfunction "C_C") (pintype "passive"))
      (node (ref "T6") (pin "C") (pinfunction "C_C") (pintype "passive"))
      (node (ref "U$1") (pin "4") (pinfunction "GND_4") (pintype "power_in"))
      (node (ref "U$1") (pin "6") (pinfunction "RL_6") (pintype "bidirectional"))
      (node (ref "U1") (pin "2") (pinfunction "2_2") (pintype "passive"))
      (node (ref "U2") (pin "9") (pinfunction "9_9") (pintype "passive"))
      (node (ref "U3") (pin "2") (pinfunction "2_2") (pintype "passive"))
      (node (ref "VOLUME") (pin "4") (pinfunction "P$1_4") (pintype "power_in"))
      (node (ref "VOLUME") (pin "5") (pinfunction "P$2_5") (pintype "power_in"))
    )
    (net (code "10") (name "Net-(C1-Pad1)") (class "Default")
      (node (ref "C1") (pin "1") (pinfunction "1_1") (pintype "passive"))
      (node (ref "C2") (pin "2") (pinfunction "2_2") (pintype "passive"))
      (node (ref "R28") (pin "2") (pinfunction "2_2") (pintype "passive"))
    )
    (net (code "11") (name "Net-(C1-Pad2)") (class "Default")
      (node (ref "C1") (pin "2") (pinfunction "2_2") (pintype "passive"))
      (node (ref "U1") (pin "5") (pinfunction "5_5") (pintype "passive"))
    )
    (net (code "12") (name "Net-(C4-Pad-)") (class "Default")
      (node (ref "C4") (pin "-") (pinfunction "-_-") (pintype "passive"))
      (node (ref "R15") (pin "2") (pinfunction "2_2") (pintype "passive"))
      (node (ref "R31") (pin "1") (pinfunction "1_1") (pintype "passive"))
    )
    (net (code "13") (name "Net-(C18-Pad1)") (class "Default")
      (node (ref "C18") (pin "1") (pinfunction "1_1") (pintype "passive"))
      (node (ref "PTT") (pin "MP") (pinfunction "MP_MP") (pintype "passive"))
      (node (ref "R8") (pin "2") (pinfunction "2_2") (pintype "passive"))
    )
    (net (code "14") (name "Net-(C25-Pad2)") (class "Default")
      (node (ref "C25") (pin "2") (pinfunction "2_2") (pintype "passive"))
      (node (ref "D1") (pin "A") (pinfunction "A_A") (pintype "passive"))
      (node (ref "D2") (pin "A") (pinfunction "A_A") (pintype "passive"))
      (node (ref "D3") (pin "A") (pinfunction "A_A") (pintype "passive"))
      (node (ref "U1") (pin "1") (pinfunction "1_1") (pintype "passive"))
    )
    (net (code "15") (name "Net-(C32-Pad2)") (class "Default")
      (node (ref "C32") (pin "2") (pinfunction "2_2") (pintype "passive"))
      (node (ref "R2") (pin "2") (pinfunction "2_2") (pintype "passive"))
      (node (ref "R4") (pin "2") (pinfunction "2_2") (pintype "passive"))
      (node (ref "U2") (pin "5") (pinfunction "5_5") (pintype "passive"))
    )
    (net (code "16") (name "Net-(CLARIFIER-A)") (class "Default")
      (node (ref "CLARIFIER") (pin "3") (pinfunction "A_3") (pintype "passive"))
      (node (ref "R6") (pin "1") (pinfunction "1_1") (pintype "passive"))
    )
    (net (code "17") (name "Net-(CLARIFIER-E)") (class "Default")
      (node (ref "CLARIFIER") (pin "1") (pinfunction "E_1") (pintype "passive"))
      (node (ref "R5") (pin "1") (pinfunction "1_1") (pintype "passive"))
    )
    (net (code "18") (name "Net-(CLARIFIER-S)") (class "Default")
      (node (ref "CLARIFIER") (pin "2") (pinfunction "S_2") (pintype "passive"))
      (node (ref "U2") (pin "7") (pinfunction "7_7") (pintype "passive"))
    )
    (net (code "19") (name "Net-(D4-PadC)") (class "Default")
      (node (ref "D4") (pin "C") (pinfunction "C_C") (pintype "passive"))
      (node (ref "R4") (pin "1") (pinfunction "1_1") (pintype "passive"))
      (node (ref "R5") (pin "2") (pinfunction "2_2") (pintype "passive"))
    )
    (net (code "20") (name "Net-(DISPLAY1-D1_A)") (class "Default")
      (node (ref "C15") (pin "+") (pinfunction "+_+") (pintype "passive"))
      (node (ref "C19") (pin "2") (pinfunction "2_2") (pintype "passive"))
      (node (ref "C33") (pin "+") (pinfunction "+_+") (pintype "passive"))
      (node (ref "C34") (pin "+") (pinfunction "+_+") (pintype "passive"))
      (node (ref "DISPLAY1") (pin "A1") (pinfunction "D1_A_A1") (pintype "input"))
      (node (ref "DISPLAY1") (pin "A2") (pinfunction "D2_A_A2") (pintype "input"))
      (node (ref "DISPLAY1") (pin "A3") (pinfunction "D3_A_A3") (pintype "input"))
      (node (ref "DISPLAY1") (pin "A4") (pinfunction "D4_A_A4") (pintype "input"))
      (node (ref "IC2") (pin "8") (pinfunction "V+_8") (pintype "power_in"))
      (node (ref "LED01") (pin "A") (pinfunction "A_A") (pintype "passive"))
      (node (ref "LED02") (pin "A") (pinfunction "A_A") (pintype "passive"))
      (node (ref "LED03") (pin "A") (pinfunction "A_A") (pintype "passive"))
      (node (ref "LED04") (pin "A") (pinfunction "A_A") (pintype "passive"))
      (node (ref "LED05") (pin "A") (pinfunction "A_A") (pintype "passive"))
      (node (ref "LED06") (pin "A") (pinfunction "A_A") (pintype "passive"))
      (node (ref "LED07") (pin "A") (pinfunction "A_A") (pintype "passive"))
      (node (ref "LED08") (pin "A") (pinfunction "A_A") (pintype "passive"))
      (node (ref "LED09") (pin "A") (pinfunction "A_A") (pintype "passive"))
      (node (ref "LED10") (pin "A") (pinfunction "A_A") (pintype "passive"))
      (node (ref "LED11") (pin "A") (pinfunction "A_A") (pintype "passive"))
      (node (ref "LED12") (pin "A") (pinfunction "A_A") (pintype "passive"))
      (node (ref "LED13") (pin "A") (pinfunction "A_A") (pintype "passive"))
      (node (ref "LED14") (pin "A") (pinfunction "A_A") (pintype "passive"))
      (node (ref "LED15") (pin "A") (pinfunction "A_A") (pintype "passive"))
      (node (ref "LED16") (pin "A") (pinfunction "A_A") (pintype "passive"))
      (node (ref "LED17") (pin "A") (pinfunction "A_A") (pintype "passive"))
      (node (ref "LED18") (pin "A") (pinfunction "A_A") (pintype "passive"))
      (node (ref "LED19") (pin "A") (pinfunction "A_A") (pintype "passive"))
      (node (ref "LED20") (pin "A") (pinfunction "A_A") (pintype "passive"))
      (node (ref "R17") (pin "2") (pinfunction "2_2") (pintype "passive"))
      (node (ref "R18") (pin "2") (pinfunction "2_2") (pintype "passive"))
      (node (ref "U1") (pin "4") (pinfunction "4_4") (pintype "passive"))
    )
    (net (code "21") (name "Net-(DISPLAY1-D1_K)") (class "Default")
      (node (ref "DISPLAY1") (pin "K1") (pinfunction "D1_K_K1") (pintype "input"))
      (node (ref "IC3") (pin "17") (pinfunction "/OUT10_17") (pintype "bidirectional"))
    )
    (net (code "22") (name "Net-(DISPLAY1-D2_K)") (class "Default")
      (node (ref "DISPLAY1") (pin "K2") (pinfunction "D2_K_K2") (pintype "input"))
      (node (ref "IC3") (pin "18") (pinfunction "/OUT11_18") (pintype "bidirectional"))
    )
    (net (code "23") (name "Net-(DISPLAY1-D3_K)") (class "Default")
      (node (ref "DISPLAY1") (pin "K3") (pinfunction "D3_K_K3") (pintype "input"))
      (node (ref "IC4") (pin "17") (pinfunction "/OUT10_17") (pintype "bidirectional"))
    )
    (net (code "24") (name "Net-(DISPLAY1-D4_K)") (class "Default")
      (node (ref "DISPLAY1") (pin "K4") (pinfunction "D4_K_K4") (pintype "input"))
      (node (ref "IC4") (pin "18") (pinfunction "/OUT11_18") (pintype "bidirectional"))
    )
    (net (code "25") (name "Net-(IC1-(A11)PC3)") (class "Default")
      (node (ref "C29") (pin "2") (pinfunction "2_2") (pintype "passive"))
      (node (ref "IC1") (pin "38") (pinfunction "(A11)PC3_38") (pintype "output"))
      (node (ref "PC3") (pin "MP") (pinfunction "MP_MP") (pintype "passive"))
    )
    (net (code "26") (name "Net-(IC1-(A12)PC4)") (class "Default")
      (node (ref "C28") (pin "2") (pinfunction "2_2") (pintype "passive"))
      (node (ref "IC1") (pin "39") (pinfunction "(A12)PC4_39") (pintype "output"))
      (node (ref "PC4") (pin "MP") (pinfunction "MP_MP") (pintype "passive"))
    )
    (net (code "27") (name "Net-(IC1-(A13)PC5)") (class "Default")
      (node (ref "C27") (pin "2") (pinfunction "2_2") (pintype "passive"))
      (node (ref "IC1") (pin "40") (pinfunction "(A13)PC5_40") (pintype "output"))
      (node (ref "PC5") (pin "MP") (pinfunction "MP_MP") (pintype "passive"))
    )
    (net (code "28") (name "Net-(IC1-(AD2)PA2)") (class "Default")
      (node (ref "C26") (pin "2") (pinfunction "2_2") (pintype "passive"))
      (node (ref "IC1") (pin "49") (pinfunction "(AD2)PA2_49") (pintype "bidirectional"))
      (node (ref "R29") (pin "2") (pinfunction "2_2") (pintype "passive"))
      (node (ref "U1") (pin "6") (pinfunction "6_6") (pintype "passive"))
    )
    (net (code "29") (name "Net-(IC1-(AD3)PA3)") (class "Default")
      (node (ref "C11") (pin "2") (pinfunction "2_2") (pintype "passive"))
      (node (ref "IC1") (pin "48") (pinfunction "(AD3)PA3_48") (pintype "bidirectional"))
      (node (ref "U1") (pin "8") (pinfunction "8_8") (pintype "passive"))
    )
    (net (code "30") (name "Net-(IC1-(AD4)PA4)") (class "Default")
      (node (ref "C12") (pin "2") (pinfunction "2_2") (pintype "passive"))
      (node (ref "IC1") (pin "47") (pinfunction "(AD4)PA4_47") (pintype "bidirectional"))
      (node (ref "U1") (pin "10") (pinfunction "10_10") (pintype "passive"))
    )
    (net (code "31") (name "Net-(IC1-(AD5)PA5)") (class "Default")
      (node (ref "C10") (pin "2") (pinfunction "2_2") (pintype "passive"))
      (node (ref "IC1") (pin "46") (pinfunction "(AD5)PA5_46") (pintype "bidirectional"))
      (node (ref "U1") (pin "9") (pinfunction "9_9") (pintype "passive"))
    )
    (net (code "32") (name "Net-(IC1-(AD6)PA6)") (class "Default")
      (node (ref "C9") (pin "2") (pinfunction "2_2") (pintype "passive"))
      (node (ref "IC1") (pin "45") (pinfunction "(AD6)PA6_45") (pintype "bidirectional"))
      (node (ref "U1") (pin "7") (pinfunction "7_7") (pintype "passive"))
    )
    (net (code "33") (name "Net-(IC1-(AD7)PA7)") (class "Default")
      (node (ref "IC1") (pin "44") (pinfunction "(AD7)PA7_44") (pintype "bidirectional"))
      (node (ref "R12") (pin "1") (pinfunction "1_1") (pintype "passive"))
    )
    (net (code "34") (name "Net-(IC1-(IC3{slash}INT7)PE7)") (class "Default")
      (node (ref "C3") (pin "+") (pinfunction "+_+") (pintype "passive"))
      (node (ref "IC1") (pin "9") (pinfunction "(IC3/INT7)PE7_9") (pintype "bidirectional"))
      (node (ref "R25") (pin "1") (pinfunction "1_1") (pintype "passive"))
    )
    (net (code "35") (name "Net-(IC1-(MISO)PB3)") (class "Default")
      (node (ref "IC1") (pin "13") (pinfunction "(MISO)PB3_13") (pintype "bidirectional"))
      (node (ref "IC7") (pin "2") (pinfunction "SO_2") (pintype "bidirectional"))
    )
    (net (code "36") (name "Net-(IC1-(MOSI)PB2)") (class "Default")
      (node (ref "IC1") (pin "12") (pinfunction "(MOSI)PB2_12") (pintype "bidirectional"))
      (node (ref "IC7") (pin "5") (pinfunction "SI_5") (pintype "input"))
    )
    (net (code "37") (name "Net-(IC1-(OC1A)PB5)") (class "Default")
      (node (ref "IC1") (pin "15") (pinfunction "(OC1A)PB5_15") (pintype "bidirectional"))
      (node (ref "U$1") (pin "5") (pinfunction "RW_5") (pintype "bidirectional"))
    )
    (net (code "38") (name "Net-(IC1-(OC3A{slash}AIN1)PE3)") (class "Default")
      (node (ref "IC1") (pin "5") (pinfunction "(OC3A/AIN1)PE3_5") (pintype "bidirectional"))
      (node (ref "SPK") (pin "MP") (pinfunction "MP_MP") (pintype "passive"))
    )
    (net (code "39") (name "Net-(IC1-(OC3B{slash}INT4)PE4)") (class "Default")
      (node (ref "C31") (pin "1") (pinfunction "1_1") (pintype "passive"))
      (node (ref "D3") (pin "C") (pinfunction "C_C") (pintype "passive"))
      (node (ref "IC1") (pin "6") (pinfunction "(OC3B/INT4)PE4_6") (pintype "bidirectional"))
      (node (ref "R23") (pin "2") (pinfunction "2_2") (pintype "passive"))
    )
    (net (code "40") (name "Net-(IC1-(OC3C{slash}INT5)PE5)") (class "Default")
      (node (ref "IC1") (pin "7") (pinfunction "(OC3C/INT5)PE5_7") (pintype "bidirectional"))
      (node (ref "SW01") (pin "3") (pinfunction "3_3") (pintype "passive"))
      (node (ref "SW01") (pin "4") (pinfunction "4_4") (pintype "passive"))
    )
    (net (code "41") (name "Net-(IC1-(SS)PB0)") (class "Default")
      (node (ref "IC1") (pin "10") (pinfunction "(SS)PB0_10") (pintype "bidirectional"))
      (node (ref "IC7") (pin "1") (pinfunction "~{CS}_1") (pintype "input"))
    )
    (net (code "42") (name "Net-(IC1-(T3{slash}INT6)PE6)") (class "Default")
      (node (ref "C30") (pin "1") (pinfunction "1_1") (pintype "passive"))
      (node (ref "IC1") (pin "8") (pinfunction "(T3/INT6)PE6_8") (pintype "bidirectional"))
      (node (ref "PE6") (pin "MP") (pinfunction "MP_MP") (pintype "passive"))
    )
    (net (code "43") (name "Net-(IC1-AVCC)") (class "Default")
      (node (ref "C7") (pin "2") (pinfunction "2_2") (pintype "passive"))
      (node (ref "IC1") (pin "64") (pinfunction "AVCC_64") (pintype "power_in"))
      (node (ref "L1") (pin "1") (pinfunction "1_1") (pintype "passive"))
    )
    (net (code "44") (name "Net-(IC1-PF1(ADC1))") (class "Default")
      (node (ref "IC1") (pin "60") (pinfunction "PF1(ADC1)_60") (pintype "input"))
      (node (ref "SWR/CAL") (pin "3") (pinfunction "A_3") (pintype "passive"))
      (node (ref "U2") (pin "10") (pinfunction "10_10") (pintype "passive"))
    )
    (net (code "45") (name "Net-(IC1-XTAL1)") (class "Default")
      (node (ref "C6") (pin "2") (pinfunction "2_2") (pintype "passive"))
      (node (ref "IC1") (pin "24") (pinfunction "XTAL1_24") (pintype "bidirectional"))
      (node (ref "Q1") (pin "2") (pinfunction "2_2") (pintype "passive"))
    )
    (net (code "46") (name "Net-(IC1-XTAL2)") (class "Default")
      (node (ref "C5") (pin "2") (pinfunction "2_2") (pintype "passive"))
      (node (ref "IC1") (pin "23") (pinfunction "XTAL2_23") (pintype "bidirectional"))
      (node (ref "Q1") (pin "1") (pinfunction "1_1") (pintype "passive"))
    )
    (net (code "47") (name "Net-(IC2A-+IN)") (class "Default")
      (node (ref "C20") (pin "2") (pinfunction "2_2") (pintype "passive"))
      (node (ref "IC2") (pin "3") (pinfunction "+IN_3") (pintype "input"))
      (node (ref "IC2") (pin "6") (pinfunction "-IN_6") (pintype "input"))
      (node (ref "R10") (pin "2") (pinfunction "2_2") (pintype "passive"))
      (node (ref "R17") (pin "1") (pinfunction "1_1") (pintype "passive"))
      (node (ref "UP/DOWN") (pin "MP") (pinfunction "MP_MP") (pintype "passive"))
    )
    (net (code "48") (name "Net-(IC2A--IN)") (class "Default")
      (node (ref "IC2") (pin "2") (pinfunction "-IN_2") (pintype "input"))
      (node (ref "R18") (pin "1") (pinfunction "1_1") (pintype "passive"))
      (node (ref "R19") (pin "2") (pinfunction "2_2") (pintype "passive"))
    )
    (net (code "49") (name "Net-(IC2A-OUT)") (class "Default")
      (node (ref "IC2") (pin "1") (pinfunction "OUT_1") (pintype "output"))
      (node (ref "R11") (pin "2") (pinfunction "2_2") (pintype "passive"))
      (node (ref "R21") (pin "2") (pinfunction "2_2") (pintype "passive"))
    )
    (net (code "50") (name "Net-(IC2B-+IN)") (class "Default")
      (node (ref "IC2") (pin "5") (pinfunction "+IN_5") (pintype "input"))
      (node (ref "R19") (pin "1") (pinfunction "1_1") (pintype "passive"))
      (node (ref "R20") (pin "2") (pinfunction "2_2") (pintype "passive"))
    )
    (net (code "51") (name "Net-(IC2B-OUT)") (class "Default")
      (node (ref "IC2") (pin "7") (pinfunction "OUT_7") (pintype "output"))
      (node (ref "R1") (pin "2") (pinfunction "2_2") (pintype "passive"))
      (node (ref "R22") (pin "2") (pinfunction "2_2") (pintype "passive"))
    )
    (net (code "52") (name "Net-(IC3-REXT)") (class "Default")
      (node (ref "IC3") (pin "1") (pinfunction "REXT_1") (pintype "bidirectional"))
      (node (ref "R3") (pin "2") (pinfunction "2_2") (pintype "passive"))
    )
    (net (code "53") (name "Net-(IC3-{slash}OUT0)") (class "Default")
      (node (ref "IC3") (pin "6") (pinfunction "/OUT0_6") (pintype "bidirectional"))
      (node (ref "LED11") (pin "C") (pinfunction "C_C") (pintype "passive"))
    )
    (net (code "54") (name "Net-(IC3-{slash}OUT1)") (class "Default")
      (node (ref "IC3") (pin "7") (pinfunction "/OUT1_7") (pintype "bidirectional"))
      (node (ref "LED12") (pin "C") (pinfunction "C_C") (pintype "passive"))
    )
    (net (code "55") (name "Net-(IC3-{slash}OUT2)") (class "Default")
      (node (ref "IC3") (pin "8") (pinfunction "/OUT2_8") (pintype "bidirectional"))
      (node (ref "LED13") (pin "C") (pinfunction "C_C") (pintype "passive"))
    )
    (net (code "56") (name "Net-(IC3-{slash}OUT3)") (class "Default")
      (node (ref "IC3") (pin "9") (pinfunction "/OUT3_9") (pintype "bidirectional"))
      (node (ref "LED14") (pin "C") (pinfunction "C_C") (pintype "passive"))
    )
    (net (code "57") (name "Net-(IC3-{slash}OUT4)") (class "Default")
      (node (ref "IC3") (pin "11") (pinfunction "/OUT4_11") (pintype "bidirectional"))
      (node (ref "LED15") (pin "C") (pinfunction "C_C") (pintype "passive"))
    )
    (net (code "58") (name "Net-(IC3-{slash}OUT5)") (class "Default")
      (node (ref "IC3") (pin "12") (pinfunction "/OUT5_12") (pintype "bidirectional"))
      (node (ref "LED16") (pin "C") (pinfunction "C_C") (pintype "passive"))
    )
    (net (code "59") (name "Net-(IC3-{slash}OUT6)") (class "Default")
      (node (ref "IC3") (pin "13") (pinfunction "/OUT6_13") (pintype "bidirectional"))
      (node (ref "LED17") (pin "C") (pinfunction "C_C") (pintype "passive"))
    )
    (net (code "60") (name "Net-(IC3-{slash}OUT7)") (class "Default")
      (node (ref "IC3") (pin "14") (pinfunction "/OUT7_14") (pintype "bidirectional"))
      (node (ref "LED18") (pin "C") (pinfunction "C_C") (pintype "passive"))
    )
    (net (code "61") (name "Net-(IC3-{slash}OUT8)") (class "Default")
      (node (ref "IC3") (pin "15") (pinfunction "/OUT8_15") (pintype "bidirectional"))
      (node (ref "LED19") (pin "C") (pinfunction "C_C") (pintype "passive"))
    )
    (net (code "62") (name "Net-(IC3-{slash}OUT9)") (class "Default")
      (node (ref "IC3") (pin "16") (pinfunction "/OUT9_16") (pintype "bidirectional"))
      (node (ref "LED20") (pin "C") (pinfunction "C_C") (pintype "passive"))
    )
    (net (code "63") (name "Net-(IC3-{slash}RESET)") (class "Default")
      (node (ref "IC3") (pin "25") (pinfunction "/RESET_25") (pintype "bidirectional"))
      (node (ref "R13") (pin "2") (pinfunction "2_2") (pintype "passive"))
    )
    (net (code "64") (name "Net-(IC4-REXT)") (class "Default")
      (node (ref "IC4") (pin "1") (pinfunction "REXT_1") (pintype "bidirectional"))
      (node (ref "R16") (pin "2") (pinfunction "2_2") (pintype "passive"))
    )
    (net (code "65") (name "Net-(IC4-{slash}OUT0)") (class "Default")
      (node (ref "IC4") (pin "6") (pinfunction "/OUT0_6") (pintype "bidirectional"))
      (node (ref "LED01") (pin "C") (pinfunction "C_C") (pintype "passive"))
    )
    (net (code "66") (name "Net-(IC4-{slash}OUT1)") (class "Default")
      (node (ref "IC4") (pin "7") (pinfunction "/OUT1_7") (pintype "bidirectional"))
      (node (ref "LED02") (pin "C") (pinfunction "C_C") (pintype "passive"))
    )
    (net (code "67") (name "Net-(IC4-{slash}OUT2)") (class "Default")
      (node (ref "IC4") (pin "8") (pinfunction "/OUT2_8") (pintype "bidirectional"))
      (node (ref "LED03") (pin "C") (pinfunction "C_C") (pintype "passive"))
    )
    (net (code "68") (name "Net-(IC4-{slash}OUT3)") (class "Default")
      (node (ref "IC4") (pin "9") (pinfunction "/OUT3_9") (pintype "bidirectional"))
      (node (ref "LED04") (pin "C") (pinfunction "C_C") (pintype "passive"))
    )
    (net (code "69") (name "Net-(IC4-{slash}OUT4)") (class "Default")
      (node (ref "IC4") (pin "11") (pinfunction "/OUT4_11") (pintype "bidirectional"))
      (node (ref "LED05") (pin "C") (pinfunction "C_C") (pintype "passive"))
    )
    (net (code "70") (name "Net-(IC4-{slash}OUT5)") (class "Default")
      (node (ref "IC4") (pin "12") (pinfunction "/OUT5_12") (pintype "bidirectional"))
      (node (ref "LED06") (pin "C") (pinfunction "C_C") (pintype "passive"))
    )
    (net (code "71") (name "Net-(IC4-{slash}OUT6)") (class "Default")
      (node (ref "IC4") (pin "13") (pinfunction "/OUT6_13") (pintype "bidirectional"))
      (node (ref "LED07") (pin "C") (pinfunction "C_C") (pintype "passive"))
    )
    (net (code "72") (name "Net-(IC4-{slash}OUT7)") (class "Default")
      (node (ref "IC4") (pin "14") (pinfunction "/OUT7_14") (pintype "bidirectional"))
      (node (ref "LED08") (pin "C") (pinfunction "C_C") (pintype "passive"))
    )
    (net (code "73") (name "Net-(IC4-{slash}OUT8)") (class "Default")
      (node (ref "IC4") (pin "15") (pinfunction "/OUT8_15") (pintype "bidirectional"))
      (node (ref "LED09") (pin "C") (pinfunction "C_C") (pintype "passive"))
    )
    (net (code "74") (name "Net-(IC4-{slash}OUT9)") (class "Default")
      (node (ref "IC4") (pin "16") (pinfunction "/OUT9_16") (pintype "bidirectional"))
      (node (ref "LED10") (pin "C") (pinfunction "C_C") (pintype "passive"))
    )
    (net (code "75") (name "Net-(IC4-{slash}RESET)") (class "Default")
      (node (ref "IC4") (pin "25") (pinfunction "/RESET_25") (pintype "bidirectional"))
      (node (ref "R33") (pin "2") (pinfunction "2_2") (pintype "passive"))
    )
    (net (code "76") (name "Net-(IC5-I{slash}O0.0)") (class "Default")
      (node (ref "IC5") (pin "4") (pinfunction "I/O0.0_4") (pintype "bidirectional"))
      (node (ref "SW13") (pin "3") (pinfunction "3_3") (pintype "passive"))
      (node (ref "SW13") (pin "4") (pinfunction "4_4") (pintype "passive"))
    )
    (net (code "77") (name "Net-(IC5-I{slash}O0.1)") (class "Default")
      (node (ref "IC5") (pin "5") (pinfunction "I/O0.1_5") (pintype "bidirectional"))
      (node (ref "SW14") (pin "3") (pinfunction "3_3") (pintype "passive"))
      (node (ref "SW14") (pin "4") (pinfunction "4_4") (pintype "passive"))
    )
    (net (code "78") (name "Net-(IC5-I{slash}O0.2)") (class "Default")
      (node (ref "IC5") (pin "6") (pinfunction "I/O0.2_6") (pintype "bidirectional"))
      (node (ref "SW15") (pin "3") (pinfunction "3_3") (pintype "passive"))
      (node (ref "SW15") (pin "4") (pinfunction "4_4") (pintype "passive"))
    )
    (net (code "79") (name "Net-(IC5-I{slash}O0.6)") (class "Default")
      (node (ref "IC5") (pin "10") (pinfunction "I/O0.6_10") (pintype "bidirectional"))
      (node (ref "T5") (pin "E") (pinfunction "E_E") (pintype "passive"))
    )
    (net (code "80") (name "Net-(IC5-I{slash}O0.7)") (class "Default")
      (node (ref "IC5") (pin "11") (pinfunction "I/O0.7_11") (pintype "bidirectional"))
      (node (ref "T6") (pin "E") (pinfunction "E_E") (pintype "passive"))
    )
    (net (code "81") (name "Net-(IC5-I{slash}O1.0)") (class "Default")
      (node (ref "IC5") (pin "13") (pinfunction "I/O1.0_13") (pintype "bidirectional"))
      (node (ref "SW20") (pin "3") (pinfunction "3_3") (pintype "passive"))
      (node (ref "SW20") (pin "4") (pinfunction "4_4") (pintype "passive"))
    )
    (net (code "82") (name "Net-(IC5-I{slash}O1.1)") (class "Default")
      (node (ref "C21") (pin "2") (pinfunction "2_2") (pintype "passive"))
      (node (ref "IC5") (pin "14") (pinfunction "I/O1.1_14") (pintype "bidirectional"))
      (node (ref "SW22") (pin "B") (pinfunction "B_B") (pintype "passive"))
    )
    (net (code "83") (name "Net-(IC5-I{slash}O1.2)") (class "Default")
      (node (ref "C22") (pin "2") (pinfunction "2_2") (pintype "passive"))
      (node (ref "IC5") (pin "15") (pinfunction "I/O1.2_15") (pintype "bidirectional"))
      (node (ref "SW22") (pin "A") (pinfunction "A_A") (pintype "passive"))
    )
    (net (code "84") (name "Net-(IC5-I{slash}O1.3)") (class "Default")
      (node (ref "IC5") (pin "16") (pinfunction "I/O1.3_16") (pintype "bidirectional"))
      (node (ref "SW21") (pin "3") (pinfunction "3_3") (pintype "passive"))
      (node (ref "SW21") (pin "4") (pinfunction "4_4") (pintype "passive"))
    )
    (net (code "85") (name "Net-(IC5-I{slash}O1.4)") (class "Default")
      (node (ref "IC5") (pin "17") (pinfunction "I/O1.4_17") (pintype "bidirectional"))
      (node (ref "SW18") (pin "3") (pinfunction "3_3") (pintype "passive"))
      (node (ref "SW18") (pin "4") (pinfunction "4_4") (pintype "passive"))
    )
    (net (code "86") (name "Net-(IC5-I{slash}O1.5)") (class "Default")
      (node (ref "IC5") (pin "18") (pinfunction "I/O1.5_18") (pintype "bidirectional"))
      (node (ref "SW19") (pin "3") (pinfunction "3_3") (pintype "passive"))
      (node (ref "SW19") (pin "4") (pinfunction "4_4") (pintype "passive"))
    )
    (net (code "87") (name "Net-(IC5-I{slash}O1.6)") (class "Default")
      (node (ref "IC5") (pin "19") (pinfunction "I/O1.6_19") (pintype "bidirectional"))
      (node (ref "SW16") (pin "3") (pinfunction "3_3") (pintype "passive"))
      (node (ref "SW16") (pin "4") (pinfunction "4_4") (pintype "passive"))
    )
    (net (code "88") (name "Net-(IC5-I{slash}O1.7)") (class "Default")
      (node (ref "IC5") (pin "20") (pinfunction "I/O1.7_20") (pintype "bidirectional"))
      (node (ref "SW17") (pin "3") (pinfunction "3_3") (pintype "passive"))
      (node (ref "SW17") (pin "4") (pinfunction "4_4") (pintype "passive"))
    )
    (net (code "89") (name "Net-(IC5-~{INT})") (class "Default")
      (node (ref "IC5") (pin "1") (pinfunction "~{INT}_1") (pintype "output"))
      (node (ref "IC6") (pin "1") (pinfunction "~{INT}_1") (pintype "output"))
      (node (ref "R25") (pin "2") (pinfunction "2_2") (pintype "passive"))
    )
    (net (code "90") (name "Net-(IC6-I{slash}O0.0)") (class "Default")
      (node (ref "IC6") (pin "4") (pinfunction "I/O0.0_4") (pintype "bidirectional"))
      (node (ref "SW08") (pin "3") (pinfunction "3_3") (pintype "passive"))
      (node (ref "SW08") (pin "4") (pinfunction "4_4") (pintype "passive"))
    )
    (net (code "91") (name "Net-(IC6-I{slash}O0.1)") (class "Default")
      (node (ref "IC6") (pin "5") (pinfunction "I/O0.1_5") (pintype "bidirectional"))
      (node (ref "SW07") (pin "3") (pinfunction "3_3") (pintype "passive"))
      (node (ref "SW07") (pin "4") (pinfunction "4_4") (pintype "passive"))
    )
    (net (code "92") (name "Net-(IC6-I{slash}O0.2)") (class "Default")
      (node (ref "IC6") (pin "6") (pinfunction "I/O0.2_6") (pintype "bidirectional"))
      (node (ref "SW06") (pin "3") (pinfunction "3_3") (pintype "passive"))
      (node (ref "SW06") (pin "4") (pinfunction "4_4") (pintype "passive"))
    )
    (net (code "93") (name "Net-(IC6-I{slash}O0.3)") (class "Default")
      (node (ref "IC6") (pin "7") (pinfunction "I/O0.3_7") (pintype "bidirectional"))
      (node (ref "SW05") (pin "3") (pinfunction "3_3") (pintype "passive"))
      (node (ref "SW05") (pin "4") (pinfunction "4_4") (pintype "passive"))
    )
    (net (code "94") (name "Net-(IC6-I{slash}O0.4)") (class "Default")
      (node (ref "IC6") (pin "8") (pinfunction "I/O0.4_8") (pintype "bidirectional"))
      (node (ref "SW04") (pin "3") (pinfunction "3_3") (pintype "passive"))
      (node (ref "SW04") (pin "4") (pinfunction "4_4") (pintype "passive"))
    )
    (net (code "95") (name "Net-(IC6-I{slash}O0.5)") (class "Default")
      (node (ref "IC6") (pin "9") (pinfunction "I/O0.5_9") (pintype "bidirectional"))
      (node (ref "SW03") (pin "3") (pinfunction "3_3") (pintype "passive"))
      (node (ref "SW03") (pin "4") (pinfunction "4_4") (pintype "passive"))
    )
    (net (code "96") (name "Net-(IC6-I{slash}O0.6)") (class "Default")
      (node (ref "IC6") (pin "10") (pinfunction "I/O0.6_10") (pintype "bidirectional"))
      (node (ref "SW02") (pin "3") (pinfunction "3_3") (pintype "passive"))
      (node (ref "SW02") (pin "4") (pinfunction "4_4") (pintype "passive"))
    )
    (net (code "97") (name "Net-(IC6-I{slash}O1.0)") (class "Default")
      (node (ref "IC6") (pin "13") (pinfunction "I/O1.0_13") (pintype "bidirectional"))
      (node (ref "SW09") (pin "3") (pinfunction "3_3") (pintype "passive"))
      (node (ref "SW09") (pin "4") (pinfunction "4_4") (pintype "passive"))
    )
    (net (code "98") (name "Net-(IC6-I{slash}O1.1)") (class "Default")
      (node (ref "IC6") (pin "14") (pinfunction "I/O1.1_14") (pintype "bidirectional"))
      (node (ref "R8") (pin "1") (pinfunction "1_1") (pintype "passive"))
      (node (ref "R9") (pin "2") (pinfunction "2_2") (pintype "passive"))
    )
    (net (code "99") (name "Net-(IC6-I{slash}O1.2)") (class "Default")
      (node (ref "IC6") (pin "15") (pinfunction "I/O1.2_15") (pintype "bidirectional"))
      (node (ref "SW10") (pin "3") (pinfunction "3_3") (pintype "passive"))
      (node (ref "SW10") (pin "4") (pinfunction "4_4") (pintype "passive"))
    )
    (net (code "100") (name "Net-(IC6-I{slash}O1.3)") (class "Default")
      (node (ref "IC6") (pin "16") (pinfunction "I/O1.3_16") (pintype "bidirectional"))
      (node (ref "SW11") (pin "3") (pinfunction "3_3") (pintype "passive"))
      (node (ref "SW11") (pin "4") (pinfunction "4_4") (pintype "passive"))
    )
    (net (code "101") (name "Net-(IC6-I{slash}O1.4)") (class "Default")
      (node (ref "IC6") (pin "17") (pinfunction "I/O1.4_17") (pintype "bidirectional"))
      (node (ref "SW12") (pin "3") (pinfunction "3_3") (pintype "passive"))
      (node (ref "SW12") (pin "4") (pinfunction "4_4") (pintype "passive"))
    )
    (net (code "102") (name "Net-(IC8-BP0)") (class "Default")
      (node (ref "DISPLAY1") (pin "COM1") (pinfunction "COM1_COM1") (pintype "input"))
      (node (ref "IC8") (pin "25") (pinfunction "BP0_25") (pintype "output"))
    )
    (net (code "103") (name "Net-(IC8-BP1)") (class "Default")
      (node (ref "DISPLAY1") (pin "COM2") (pinfunction "COM2_COM2") (pintype "input"))
      (node (ref "IC8") (pin "26") (pinfunction "BP1_26") (pintype "output"))
    )
    (net (code "104") (name "Net-(IC8-BP2)") (class "Default")
      (node (ref "DISPLAY1") (pin "COM3") (pinfunction "COM3_COM3") (pintype "input"))
      (node (ref "IC8") (pin "27") (pinfunction "BP2_27") (pintype "output"))
    )
    (net (code "105") (name "Net-(IC8-S0)") (class "Default")
      (node (ref "DISPLAY1") (pin "SEG01") (pinfunction "SEG01_SEG01") (pintype "input"))
      (node (ref "IC8") (pin "29") (pinfunction "S0_29") (pintype "output"))
    )
    (net (code "106") (name "Net-(IC8-S1)") (class "Default")
      (node (ref "DISPLAY1") (pin "SEG02") (pinfunction "SEG02_SEG02") (pintype "input"))
      (node (ref "IC8") (pin "30") (pinfunction "S1_30") (pintype "output"))
    )
    (net (code "107") (name "Net-(IC8-S2)") (class "Default")
      (node (ref "DISPLAY1") (pin "SEG03") (pinfunction "SEG03_SEG03") (pintype "input"))
      (node (ref "IC8") (pin "31") (pinfunction "S2_31") (pintype "output"))
    )
    (net (code "108") (name "Net-(IC8-S3)") (class "Default")
      (node (ref "DISPLAY1") (pin "SEG04") (pinfunction "SEG04_SEG04") (pintype "input"))
      (node (ref "IC8") (pin "32") (pinfunction "S3_32") (pintype "output"))
    )
    (net (code "109") (name "Net-(IC8-S4)") (class "Default")
      (node (ref "DISPLAY1") (pin "SEG05") (pinfunction "SEG05_SEG05") (pintype "input"))
      (node (ref "IC8") (pin "34") (pinfunction "S4_34") (pintype "output"))
    )
    (net (code "110") (name "Net-(IC8-S5)") (class "Default")
      (node (ref "DISPLAY1") (pin "SEG06") (pinfunction "SEG06_SEG06") (pintype "input"))
      (node (ref "IC8") (pin "35") (pinfunction "S5_35") (pintype "output"))
    )
    (net (code "111") (name "Net-(IC8-S6)") (class "Default")
      (node (ref "DISPLAY1") (pin "SEG07") (pinfunction "SEG07_SEG07") (pintype "input"))
      (node (ref "IC8") (pin "36") (pinfunction "S6_36") (pintype "output"))
    )
    (net (code "112") (name "Net-(IC8-S7)") (class "Default")
      (node (ref "DISPLAY1") (pin "SEG08") (pinfunction "SEG08_SEG08") (pintype "input"))
      (node (ref "IC8") (pin "37") (pinfunction "S7_37") (pintype "output"))
    )
    (net (code "113") (name "Net-(IC8-S8)") (class "Default")
      (node (ref "DISPLAY1") (pin "SEG09") (pinfunction "SEG09_SEG09") (pintype "input"))
      (node (ref "IC8") (pin "38") (pinfunction "S8_38") (pintype "output"))
    )
    (net (code "114") (name "Net-(IC8-S9)") (class "Default")
      (node (ref "DISPLAY1") (pin "SEG10") (pinfunction "SEG10_SEG10") (pintype "input"))
      (node (ref "IC8") (pin "39") (pinfunction "S9_39") (pintype "output"))
    )
    (net (code "115") (name "Net-(IC8-S10)") (class "Default")
      (node (ref "DISPLAY1") (pin "SEG11") (pinfunction "SEG11_SEG11") (pintype "input"))
      (node (ref "IC8") (pin "40") (pinfunction "S10_40") (pintype "output"))
    )
    (net (code "116") (name "Net-(IC8-S11)") (class "Default")
      (node (ref "DISPLAY1") (pin "SEG12") (pinfunction "SEG12_SEG12") (pintype "input"))
      (node (ref "IC8") (pin "41") (pinfunction "S11_41") (pintype "output"))
    )
    (net (code "117") (name "Net-(IC8-S12)") (class "Default")
      (node (ref "DISPLAY1") (pin "SEG13") (pinfunction "SEG13_SEG13") (pintype "input"))
      (node (ref "IC8") (pin "42") (pinfunction "S12_42") (pintype "output"))
    )
    (net (code "118") (name "Net-(IC8-S13)") (class "Default")
      (node (ref "DISPLAY1") (pin "SEG14") (pinfunction "SEG14_SEG14") (pintype "input"))
      (node (ref "IC8") (pin "43") (pinfunction "S13_43") (pintype "output"))
    )
    (net (code "119") (name "Net-(IC8-S14)") (class "Default")
      (node (ref "DISPLAY1") (pin "SEG15") (pinfunction "SEG15_SEG15") (pintype "input"))
      (node (ref "IC8") (pin "44") (pinfunction "S14_44") (pintype "output"))
    )
    (net (code "120") (name "Net-(IC8-S15)") (class "Default")
      (node (ref "DISPLAY1") (pin "SEG16") (pinfunction "SEG16_SEG16") (pintype "input"))
      (node (ref "IC8") (pin "45") (pinfunction "S15_45") (pintype "output"))
    )
    (net (code "121") (name "Net-(IC8-S16)") (class "Default")
      (node (ref "DISPLAY1") (pin "SEG17") (pinfunction "SEG17_SEG17") (pintype "input"))
      (node (ref "IC8") (pin "46") (pinfunction "S16_46") (pintype "output"))
    )
    (net (code "122") (name "Net-(IC8-S17)") (class "Default")
      (node (ref "DISPLAY1") (pin "SEG18") (pinfunction "SEG18_SEG18") (pintype "input"))
      (node (ref "IC8") (pin "47") (pinfunction "S17_47") (pintype "output"))
    )
    (net (code "123") (name "Net-(IC8-S18)") (class "Default")
      (node (ref "DISPLAY1") (pin "SEG19") (pinfunction "SEG19_SEG19") (pintype "input"))
      (node (ref "IC8") (pin "49") (pinfunction "S18_49") (pintype "output"))
    )
    (net (code "124") (name "Net-(IC8-S19)") (class "Default")
      (node (ref "DISPLAY1") (pin "SEG20") (pinfunction "SEG20_SEG20") (pintype "input"))
      (node (ref "IC8") (pin "50") (pinfunction "S19_50") (pintype "output"))
    )
    (net (code "125") (name "Net-(IC8-S20)") (class "Default")
      (node (ref "DISPLAY1") (pin "SEG21") (pinfunction "SEG21_SEG21") (pintype "input"))
      (node (ref "IC8") (pin "51") (pinfunction "S20_51") (pintype "output"))
    )
    (net (code "126") (name "Net-(IC8-S21)") (class "Default")
      (node (ref "DISPLAY1") (pin "SEG22") (pinfunction "SEG22_SEG22") (pintype "input"))
      (node (ref "IC8") (pin "52") (pinfunction "S21_52") (pintype "output"))
    )
    (net (code "127") (name "Net-(IC8-S22)") (class "Default")
      (node (ref "DISPLAY1") (pin "SEG23") (pinfunction "SEG23_SEG23") (pintype "input"))
      (node (ref "IC8") (pin "53") (pinfunction "S22_53") (pintype "output"))
    )
    (net (code "128") (name "Net-(IC8-S23)") (class "Default")
      (node (ref "DISPLAY1") (pin "SEG24") (pinfunction "SEG24_SEG24") (pintype "input"))
      (node (ref "IC8") (pin "54") (pinfunction "S23_54") (pintype "output"))
    )
    (net (code "129") (name "Net-(IC8-S24)") (class "Default")
      (node (ref "DISPLAY1") (pin "SEG25") (pinfunction "SEG25_SEG25") (pintype "input"))
      (node (ref "IC8") (pin "55") (pinfunction "S24_55") (pintype "output"))
    )
    (net (code "130") (name "Net-(IC8-S25)") (class "Default")
      (node (ref "DISPLAY1") (pin "SEG26") (pinfunction "SEG26_SEG26") (pintype "input"))
      (node (ref "IC8") (pin "56") (pinfunction "S25_56") (pintype "output"))
    )
    (net (code "131") (name "Net-(IC8-S26)") (class "Default")
      (node (ref "DISPLAY1") (pin "SEG27") (pinfunction "SEG27_SEG27") (pintype "input"))
      (node (ref "IC8") (pin "57") (pinfunction "S26_57") (pintype "output"))
    )
    (net (code "132") (name "Net-(IC8-S27)") (class "Default")
      (node (ref "DISPLAY1") (pin "SEG28") (pinfunction "SEG28_SEG28") (pintype "input"))
      (node (ref "IC8") (pin "58") (pinfunction "S27_58") (pintype "output"))
    )
    (net (code "133") (name "Net-(IC8-S28)") (class "Default")
      (node (ref "DISPLAY1") (pin "SEG29") (pinfunction "SEG29_SEG29") (pintype "input"))
      (node (ref "IC8") (pin "59") (pinfunction "S28_59") (pintype "output"))
    )
    (net (code "134") (name "Net-(IC8-S29)") (class "Default")
      (node (ref "DISPLAY1") (pin "SEG30") (pinfunction "SEG30_SEG30") (pintype "input"))
      (node (ref "IC8") (pin "60") (pinfunction "S29_60") (pintype "output"))
    )
    (net (code "135") (name "Net-(IC8-S30)") (class "Default")
      (node (ref "DISPLAY1") (pin "SEG31") (pinfunction "SEG31_SEG31") (pintype "input"))
      (node (ref "IC8") (pin "61") (pinfunction "S30_61") (pintype "output"))
    )
    (net (code "136") (name "Net-(IC8-S31)") (class "Default")
      (node (ref "DISPLAY1") (pin "SEG32") (pinfunction "SEG32_SEG32") (pintype "input"))
      (node (ref "IC8") (pin "62") (pinfunction "S31_62") (pintype "output"))
    )
    (net (code "137") (name "Net-(IC8-S32)") (class "Default")
      (node (ref "DISPLAY1") (pin "SEG33") (pinfunction "SEG33_SEG33") (pintype "input"))
      (node (ref "IC8") (pin "63") (pinfunction "S32_63") (pintype "output"))
    )
    (net (code "138") (name "Net-(IC8-VLCD)") (class "Default")
      (node (ref "IC8") (pin "21") (pinfunction "VLCD_21") (pintype "power_in"))
      (node (ref "R30") (pin "2") (pinfunction "2_2") (pintype "passive"))
    )
    (net (code "139") (name "Net-(R1-Pad1)") (class "Default")
      (node (ref "R1") (pin "1") (pinfunction "1_1") (pintype "passive"))
      (node (ref "T6") (pin "B") (pinfunction "B_B") (pintype "passive"))
    )
    (net (code "140") (name "Net-(R7-Pad2)") (class "Default")
      (node (ref "R7") (pin "2") (pinfunction "2_2") (pintype "passive"))
      (node (ref "U2") (pin "8") (pinfunction "8_8") (pintype "passive"))
    )
    (net (code "141") (name "Net-(R11-Pad1)") (class "Default")
      (node (ref "R11") (pin "1") (pinfunction "1_1") (pintype "passive"))
      (node (ref "T5") (pin "B") (pinfunction "B_B") (pintype "passive"))
    )
    (net (code "142") (name "Net-(RF-POWER-S)") (class "Default")
      (node (ref "RF-POWER") (pin "2") (pinfunction "S_2") (pintype "passive"))
      (node (ref "U2") (pin "6") (pinfunction "6_6") (pintype "passive"))
    )
    (net (code "143") (name "Net-(SQUELCH-A)") (class "Default")
      (node (ref "R2") (pin "1") (pinfunction "1_1") (pintype "passive"))
      (node (ref "SQUELCH") (pin "3") (pinfunction "A_3") (pintype "passive"))
    )
    (net (code "144") (name "Net-(SQUELCH-S)") (class "Default")
      (node (ref "SQUELCH") (pin "2") (pinfunction "S_2") (pintype "passive"))
      (node (ref "U2") (pin "4") (pinfunction "4_4") (pintype "passive"))
    )
    (net (code "145") (name "Net-(SWR/CAL-S)") (class "Default")
      (node (ref "R7") (pin "1") (pinfunction "1_1") (pintype "passive"))
      (node (ref "SWR/CAL") (pin "2") (pinfunction "S_2") (pintype "passive"))
    )
    (net (code "146") (name "Net-(T1-B)") (class "Default")
      (node (ref "R12") (pin "2") (pinfunction "2_2") (pintype "passive"))
      (node (ref "T1") (pin "1") (pinfunction "B_1") (pintype "passive"))
    )
    (net (code "147") (name "Net-(T1-C)") (class "Default")
      (node (ref "T1") (pin "4") (pinfunction "C_4") (pintype "passive"))
      (node (ref "U1") (pin "3") (pinfunction "3_3") (pintype "passive"))
    )
    (net (code "148") (name "Net-(T4-B)") (class "Default")
      (node (ref "R15") (pin "1") (pinfunction "1_1") (pintype "passive"))
      (node (ref "T4") (pin "1") (pinfunction "B_1") (pintype "passive"))
    )
    (net (code "149") (name "Net-(T4-C)") (class "Default")
      (node (ref "R32") (pin "2") (pinfunction "2_2") (pintype "passive"))
      (node (ref "T4") (pin "4") (pinfunction "C_4") (pintype "passive"))
    )
    (net (code "150") (name "Net-(U$1-RH)") (class "Default")
      (node (ref "R28") (pin "1") (pinfunction "1_1") (pintype "passive"))
      (node (ref "U$1") (pin "7") (pinfunction "RH_7") (pintype "bidirectional"))
    )
    (net (code "151") (name "Net-(VOLUME-A)") (class "Default")
      (node (ref "U2") (pin "3") (pinfunction "3_3") (pintype "passive"))
      (node (ref "VOLUME") (pin "3") (pinfunction "A_3") (pintype "passive"))
    )
    (net (code "152") (name "Net-(VOLUME-E)") (class "Default")
      (node (ref "U2") (pin "2") (pinfunction "2_2") (pintype "passive"))
      (node (ref "VOLUME") (pin "1") (pinfunction "E_1") (pintype "passive"))
    )
    (net (code "153") (name "Net-(VOLUME-S)") (class "Default")
      (node (ref "U2") (pin "1") (pinfunction "1_1") (pintype "passive"))
      (node (ref "VOLUME") (pin "2") (pinfunction "S_2") (pintype "passive"))
    )
    (net (code "154") (name "VCC") (class "Default")
      (node (ref "5V") (pin "MP") (pinfunction "MP_MP") (pintype "passive"))
      (node (ref "C13") (pin "2") (pinfunction "2_2") (pintype "passive"))
      (node (ref "C14") (pin "2") (pinfunction "2_2") (pintype "passive"))
      (node (ref "C17") (pin "2") (pinfunction "2_2") (pintype "passive"))
      (node (ref "C23") (pin "2") (pinfunction "2_2") (pintype "passive"))
      (node (ref "C24") (pin "2") (pinfunction "2_2") (pintype "passive"))
      (node (ref "C35") (pin "2") (pinfunction "2_2") (pintype "passive"))
      (node (ref "C4") (pin "+") (pinfunction "+_+") (pintype "passive"))
      (node (ref "D2") (pin "C") (pinfunction "C_C") (pintype "passive"))
      (node (ref "IC3") (pin "28") (pinfunction "VCC_28") (pintype "bidirectional"))
      (node (ref "IC4") (pin "2") (pinfunction "A0_2") (pintype "bidirectional"))
      (node (ref "IC4") (pin "28") (pinfunction "VCC_28") (pintype "bidirectional"))
      (node (ref "IC5") (pin "21") (pinfunction "A0_21") (pintype "input"))
      (node (ref "IC5") (pin "24") (pinfunction "VDD_24") (pintype "power_in"))
      (node (ref "IC6") (pin "24") (pinfunction "VDD_24") (pintype "power_in"))
      (node (ref "IC8") (pin "14") (pinfunction "VDD_14") (pintype "power_in"))
      (node (ref "R13") (pin "1") (pinfunction "1_1") (pintype "passive"))
      (node (ref "R21") (pin "1") (pinfunction "1_1") (pintype "passive"))
      (node (ref "R22") (pin "1") (pinfunction "1_1") (pintype "passive"))
      (node (ref "R26") (pin "2") (pinfunction "2_2") (pintype "passive"))
      (node (ref "R27") (pin "2") (pinfunction "2_2") (pintype "passive"))
      (node (ref "R33") (pin "1") (pinfunction "1_1") (pintype "passive"))
      (node (ref "R9") (pin "1") (pinfunction "1_1") (pintype "passive"))
      (node (ref "U$1") (pin "1") (pinfunction "WP_1") (pintype "bidirectional"))
      (node (ref "U$1") (pin "8") (pinfunction "VCC_8") (pintype "power_in"))
      (node (ref "U3") (pin "1") (pinfunction "1_1") (pintype "passive"))
    )
    (net (code "155") (name "VCCMEM") (class "Default")
      (node (ref "C16") (pin "2") (pinfunction "2_2") (pintype "passive"))
      (node (ref "C8") (pin "2") (pinfunction "2_2") (pintype "passive"))
      (node (ref "D1") (pin "C") (pinfunction "C_C") (pintype "passive"))
      (node (ref "GC+") (pin "MP") (pinfunction "MP_MP") (pintype "passive"))
      (node (ref "IC1") (pin "21") (pinfunction "VCC_21") (pintype "power_in"))
      (node (ref "IC1") (pin "52") (pinfunction "VCC_52") (pintype "power_in"))
      (node (ref "IC7") (pin "3") (pinfunction "~{WP}_3") (pintype "input"))
      (node (ref "IC7") (pin "7") (pinfunction "~{HOLD}_7") (pintype "input"))
      (node (ref "IC7") (pin "8") (pinfunction "VCC_8") (pintype "power_in"))
      (node (ref "L1") (pin "2") (pinfunction "2_2") (pintype "passive"))
    )
    (net (code "156") (name "unconnected-(IC1-(A8)PC0-Pad35)") (class "Default")
      (node (ref "IC1") (pin "35") (pinfunction "(A8)PC0_35") (pintype "output"))
    )
    (net (code "157") (name "unconnected-(IC1-(A9)PC1-Pad36)") (class "Default")
      (node (ref "IC1") (pin "36") (pinfunction "(A9)PC1_36") (pintype "output"))
    )
    (net (code "158") (name "unconnected-(IC1-(A10)PC2-Pad37)") (class "Default")
      (node (ref "IC1") (pin "37") (pinfunction "(A10)PC2_37") (pintype "output"))
    )
    (net (code "159") (name "unconnected-(IC1-(A14)PC6-Pad41)") (class "Default")
      (node (ref "IC1") (pin "41") (pinfunction "(A14)PC6_41") (pintype "output"))
    )
    (net (code "160") (name "unconnected-(IC1-(A15)PC7-Pad42)") (class "Default")
      (node (ref "IC1") (pin "42") (pinfunction "(A15)PC7_42") (pintype "output"))
    )
    (net (code "161") (name "unconnected-(IC1-(AD0)PA0-Pad51)") (class "Default")
      (node (ref "IC1") (pin "51") (pinfunction "(AD0)PA0_51") (pintype "bidirectional"))
    )
    (net (code "162") (name "unconnected-(IC1-(AD1)PA1-Pad50)") (class "Default")
      (node (ref "IC1") (pin "50") (pinfunction "(AD1)PA1_50") (pintype "bidirectional"))
    )
    (net (code "163") (name "unconnected-(IC1-(IC1)PD4-Pad29)") (class "Default")
      (node (ref "IC1") (pin "29") (pinfunction "(IC1)PD4_29") (pintype "bidirectional"))
    )
    (net (code "164") (name "unconnected-(IC1-(OC0)PB4-Pad14)") (class "Default")
      (node (ref "IC1") (pin "14") (pinfunction "(OC0)PB4_14") (pintype "bidirectional"))
    )
    (net (code "165") (name "unconnected-(IC1-(OC1B)PB6-Pad16)") (class "Default")
      (node (ref "IC1") (pin "16") (pinfunction "(OC1B)PB6_16") (pintype "bidirectional"))
    )
    (net (code "166") (name "unconnected-(IC1-(OC2{slash}OC1C)PB7-Pad17)") (class "Default")
      (node (ref "IC1") (pin "17") (pinfunction "(OC2/OC1C)PB7_17") (pintype "bidirectional"))
    )
    (net (code "167") (name "unconnected-(IC1-(T1)PD6-Pad31)") (class "Default")
      (node (ref "IC1") (pin "31") (pinfunction "(T1)PD6_31") (pintype "bidirectional"))
    )
    (net (code "168") (name "unconnected-(IC1-(T2)PD7-Pad32)") (class "Default")
      (node (ref "IC1") (pin "32") (pinfunction "(T2)PD7_32") (pintype "bidirectional"))
    )
    (net (code "169") (name "unconnected-(IC1-(XCK0{slash}AIN0)PE2-Pad4)") (class "Default")
      (node (ref "IC1") (pin "4") (pinfunction "(XCK0/AIN0)PE2_4") (pintype "bidirectional"))
    )
    (net (code "170") (name "unconnected-(IC1-(XCK1)PD5-Pad30)") (class "Default")
      (node (ref "IC1") (pin "30") (pinfunction "(XCK1)PD5_30") (pintype "bidirectional"))
    )
    (net (code "171") (name "unconnected-(IC1-AREF-Pad62)") (class "Default")
      (node (ref "IC1") (pin "62") (pinfunction "AREF_62") (pintype "passive"))
    )
    (net (code "172") (name "unconnected-(IC1-PEN-Pad1)") (class "Default")
      (node (ref "IC1") (pin "1") (pinfunction "PEN_1") (pintype "input"))
    )
    (net (code "173") (name "unconnected-(IC1-PF2(ADC2)-Pad59)") (class "Default")
      (node (ref "IC1") (pin "59") (pinfunction "PF2(ADC2)_59") (pintype "input"))
    )
    (net (code "174") (name "unconnected-(IC1-PF3(ADC3)-Pad58)") (class "Default")
      (node (ref "IC1") (pin "58") (pinfunction "PF3(ADC3)_58") (pintype "input"))
    )
    (net (code "175") (name "unconnected-(IC1-PF4(ADC4{slash}TCK)-Pad57)") (class "Default")
      (node (ref "IC1") (pin "57") (pinfunction "PF4(ADC4/TCK)_57") (pintype "input"))
    )
    (net (code "176") (name "unconnected-(IC1-PF5(ADC5{slash}TMS)-Pad56)") (class "Default")
      (node (ref "IC1") (pin "56") (pinfunction "PF5(ADC5/TMS)_56") (pintype "input"))
    )
    (net (code "177") (name "unconnected-(IC1-PF6(ADC6{slash}TDO)-Pad55)") (class "Default")
      (node (ref "IC1") (pin "55") (pinfunction "PF6(ADC6/TDO)_55") (pintype "input"))
    )
    (net (code "178") (name "unconnected-(IC1-PF7(ADC7{slash}TDI)-Pad54)") (class "Default")
      (node (ref "IC1") (pin "54") (pinfunction "PF7(ADC7/TDI)_54") (pintype "input"))
    )
    (net (code "179") (name "unconnected-(IC1-PG0(WR)-Pad33)") (class "Default")
      (node (ref "IC1") (pin "33") (pinfunction "PG0(WR)_33") (pintype "bidirectional"))
    )
    (net (code "180") (name "unconnected-(IC1-PG1(RD)-Pad34)") (class "Default")
      (node (ref "IC1") (pin "34") (pinfunction "PG1(RD)_34") (pintype "bidirectional"))
    )
    (net (code "181") (name "unconnected-(IC1-PG2(ALE)-Pad43)") (class "Default")
      (node (ref "IC1") (pin "43") (pinfunction "PG2(ALE)_43") (pintype "bidirectional"))
    )
    (net (code "182") (name "unconnected-(IC1-PG3(TOSC2)-Pad18)") (class "Default")
      (node (ref "IC1") (pin "18") (pinfunction "PG3(TOSC2)_18") (pintype "bidirectional"))
    )
    (net (code "183") (name "unconnected-(IC1-PG4(TOSC1)-Pad19)") (class "Default")
      (node (ref "IC1") (pin "19") (pinfunction "PG4(TOSC1)_19") (pintype "bidirectional"))
    )
    (net (code "184") (name "unconnected-(IC3-{slash}OUT12-Pad20)") (class "Default")
      (node (ref "IC3") (pin "20") (pinfunction "/OUT12_20") (pintype "bidirectional"))
    )
    (net (code "185") (name "unconnected-(IC3-{slash}OUT13-Pad21)") (class "Default")
      (node (ref "IC3") (pin "21") (pinfunction "/OUT13_21") (pintype "bidirectional"))
    )
    (net (code "186") (name "unconnected-(IC3-{slash}OUT14-Pad22)") (class "Default")
      (node (ref "IC3") (pin "22") (pinfunction "/OUT14_22") (pintype "bidirectional"))
    )
    (net (code "187") (name "unconnected-(IC3-{slash}OUT15-Pad23)") (class "Default")
      (node (ref "IC3") (pin "23") (pinfunction "/OUT15_23") (pintype "bidirectional"))
    )
    (net (code "188") (name "unconnected-(IC4-{slash}OUT12-Pad20)") (class "Default")
      (node (ref "IC4") (pin "20") (pinfunction "/OUT12_20") (pintype "bidirectional"))
    )
    (net (code "189") (name "unconnected-(IC4-{slash}OUT13-Pad21)") (class "Default")
      (node (ref "IC4") (pin "21") (pinfunction "/OUT13_21") (pintype "bidirectional"))
    )
    (net (code "190") (name "unconnected-(IC4-{slash}OUT14-Pad22)") (class "Default")
      (node (ref "IC4") (pin "22") (pinfunction "/OUT14_22") (pintype "bidirectional"))
    )
    (net (code "191") (name "unconnected-(IC4-{slash}OUT15-Pad23)") (class "Default")
      (node (ref "IC4") (pin "23") (pinfunction "/OUT15_23") (pintype "bidirectional"))
    )
    (net (code "192") (name "unconnected-(IC5-I{slash}O0.3-Pad7)") (class "Default")
      (node (ref "IC5") (pin "7") (pinfunction "I/O0.3_7") (pintype "bidirectional"))
    )
    (net (code "193") (name "unconnected-(IC5-I{slash}O0.4-Pad8)") (class "Default")
      (node (ref "IC5") (pin "8") (pinfunction "I/O0.4_8") (pintype "bidirectional"))
    )
    (net (code "194") (name "unconnected-(IC5-I{slash}O0.5-Pad9)") (class "Default")
      (node (ref "IC5") (pin "9") (pinfunction "I/O0.5_9") (pintype "bidirectional"))
    )
    (net (code "195") (name "unconnected-(IC6-I{slash}O0.7-Pad11)") (class "Default")
      (node (ref "IC6") (pin "11") (pinfunction "I/O0.7_11") (pintype "bidirectional"))
    )
    (net (code "196") (name "unconnected-(IC6-I{slash}O1.5-Pad18)") (class "Default")
      (node (ref "IC6") (pin "18") (pinfunction "I/O1.5_18") (pintype "bidirectional"))
    )
    (net (code "197") (name "unconnected-(IC6-I{slash}O1.6-Pad19)") (class "Default")
      (node (ref "IC6") (pin "19") (pinfunction "I/O1.6_19") (pintype "bidirectional"))
    )
    (net (code "198") (name "unconnected-(IC6-I{slash}O1.7-Pad20)") (class "Default")
      (node (ref "IC6") (pin "20") (pinfunction "I/O1.7_20") (pintype "bidirectional"))
    )
    (net (code "199") (name "unconnected-(IC8-BP3-Pad28)") (class "Default")
      (node (ref "IC8") (pin "28") (pinfunction "BP3_28") (pintype "output"))
    )
    (net (code "200") (name "unconnected-(IC8-CLK-Pad13)") (class "Default")
      (node (ref "IC8") (pin "13") (pinfunction "CLK_13") (pintype "bidirectional"))
    )
    (net (code "201") (name "unconnected-(IC8-S33-Pad64)") (class "Default")
      (node (ref "IC8") (pin "64") (pinfunction "S33_64") (pintype "output"))
    )
    (net (code "202") (name "unconnected-(IC8-S34-Pad2)") (class "Default")
      (node (ref "IC8") (pin "2") (pinfunction "S34_2") (pintype "output"))
    )
    (net (code "203") (name "unconnected-(IC8-S35-Pad3)") (class "Default")
      (node (ref "IC8") (pin "3") (pinfunction "S35_3") (pintype "output"))
    )
    (net (code "204") (name "unconnected-(IC8-S36-Pad4)") (class "Default")
      (node (ref "IC8") (pin "4") (pinfunction "S36_4") (pintype "output"))
    )
    (net (code "205") (name "unconnected-(IC8-S37-Pad5)") (class "Default")
      (node (ref "IC8") (pin "5") (pinfunction "S37_5") (pintype "output"))
    )
    (net (code "206") (name "unconnected-(IC8-S38-Pad6)") (class "Default")
      (node (ref "IC8") (pin "6") (pinfunction "S38_6") (pintype "output"))
    )
    (net (code "207") (name "unconnected-(IC8-S39-Pad7)") (class "Default")
      (node (ref "IC8") (pin "7") (pinfunction "S39_7") (pintype "output"))
    )
    (net (code "208") (name "unconnected-(IC8-SYNC-Pad12)") (class "Default")
      (node (ref "IC8") (pin "12") (pinfunction "SYNC_12") (pintype "bidirectional"))
    )
    (net (code "209") (name "unconnected-(RF-POWER-A-Pad3)") (class "Default")
      (node (ref "RF-POWER") (pin "3") (pinfunction "A_3") (pintype "passive"))
    )
    (net (code "210") (name "unconnected-(U1-Pad11)") (class "Default")
      (node (ref "U1") (pin "11") (pinfunction "11_11") (pintype "passive"))
    )
    (net (code "211") (name "unconnected-(U1-Pad12)") (class "Default")
      (node (ref "U1") (pin "12") (pinfunction "12_12") (pintype "passive"))
    )
    (net (code "212") (name "unconnected-(U2-Pad11)") (class "Default")
      (node (ref "U2") (pin "11") (pinfunction "11_11") (pintype "passive"))
    )
    (net (code "213") (name "unconnected-(U2-Pad12)") (class "Default")
      (node (ref "U2") (pin "12") (pinfunction "12_12") (pintype "passive"))
    )
    (net (code "214") (name "unconnected-(U3-Pad7)") (class "Default")
      (node (ref "U3") (pin "7") (pinfunction "7_7") (pintype "passive"))
    )
    (net (code "215") (name "unconnected-(U3-Pad8)") (class "Default")
      (node (ref "U3") (pin "8") (pinfunction "8_8") (pintype "passive"))
    )
  )
)
